# 11-_Ethernet_MAC.net
KiCad netlist of a schematic drawn in Altium Designer
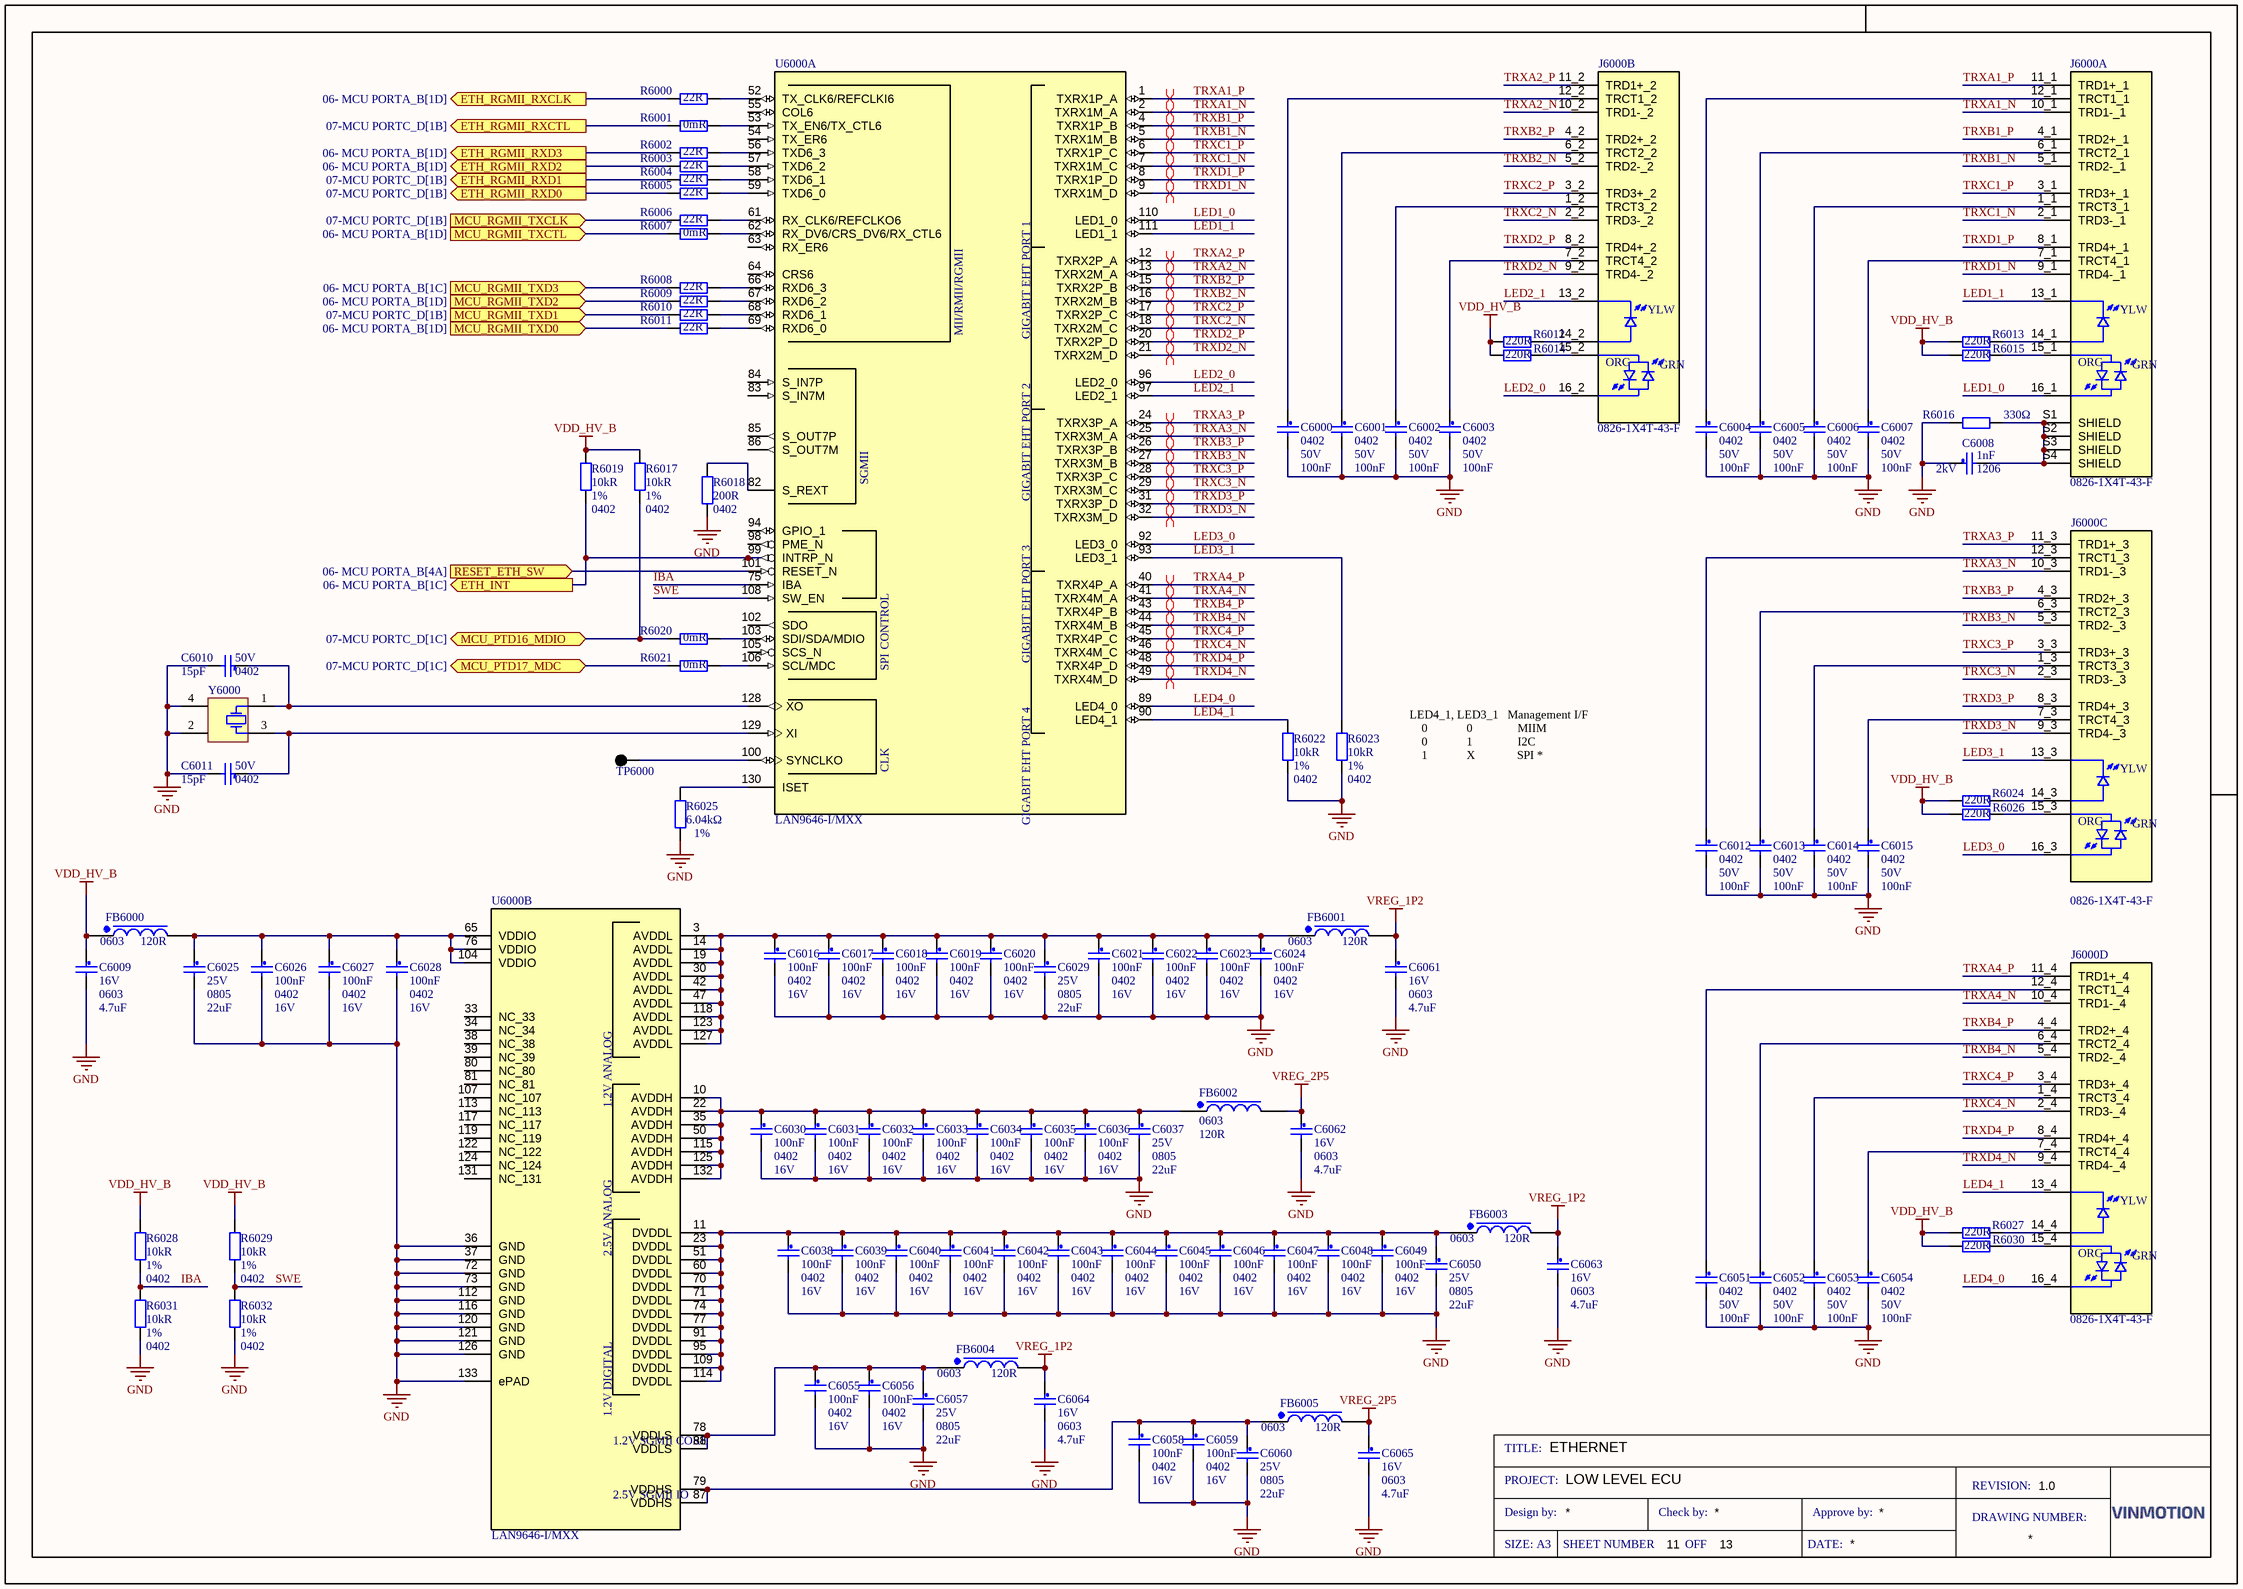
[diagram p0: 11- Ethernet MAC.SchDoc]

(export (version "E")
  (design (tool "Eeschema 10.0.6"))
  (components
    (comp (ref "C6000")
      (value "CL05B104KB54PNC")
      (footprint "CAP0402")
      (description "CAP CER 100nF 50V X7R 0402")
      (fields
        (field (name "CASE/PACKAGE") "0402")
        (field (name "VOLTAGE RATING") "50V")
        (field (name "CAPACITANCE") "100nF")
      )
      (libsource (lib "VMO_Lib") (part "CMP-00063-4"))
    )
    (comp (ref "C6001")
      (value "CL05B104KB54PNC")
      (footprint "CAP0402")
      (description "CAP CER 100nF 50V X7R 0402")
      (fields
        (field (name "CASE/PACKAGE") "0402")
        (field (name "VOLTAGE RATING") "50V")
        (field (name "CAPACITANCE") "100nF")
      )
      (libsource (lib "VMO_Lib") (part "CMP-00063-4"))
    )
    (comp (ref "C6002")
      (value "CL05B104KB54PNC")
      (footprint "CAP0402")
      (description "CAP CER 100nF 50V X7R 0402")
      (fields
        (field (name "CASE/PACKAGE") "0402")
        (field (name "VOLTAGE RATING") "50V")
        (field (name "CAPACITANCE") "100nF")
      )
      (libsource (lib "VMO_Lib") (part "CMP-00063-4"))
    )
    (comp (ref "C6003")
      (value "CL05B104KB54PNC")
      (footprint "CAP0402")
      (description "CAP CER 100nF 50V X7R 0402")
      (fields
        (field (name "CASE/PACKAGE") "0402")
        (field (name "VOLTAGE RATING") "50V")
        (field (name "CAPACITANCE") "100nF")
      )
      (libsource (lib "VMO_Lib") (part "CMP-00063-4"))
    )
    (comp (ref "C6004")
      (value "CL05B104KB54PNC")
      (footprint "CAP0402")
      (description "CAP CER 100nF 50V X7R 0402")
      (fields
        (field (name "CASE/PACKAGE") "0402")
        (field (name "VOLTAGE RATING") "50V")
        (field (name "CAPACITANCE") "100nF")
      )
      (libsource (lib "VMO_Lib") (part "CMP-00063-4"))
    )
    (comp (ref "C6005")
      (value "CL05B104KB54PNC")
      (footprint "CAP0402")
      (description "CAP CER 100nF 50V X7R 0402")
      (fields
        (field (name "CASE/PACKAGE") "0402")
        (field (name "VOLTAGE RATING") "50V")
        (field (name "CAPACITANCE") "100nF")
      )
      (libsource (lib "VMO_Lib") (part "CMP-00063-4"))
    )
    (comp (ref "C6006")
      (value "CL05B104KB54PNC")
      (footprint "CAP0402")
      (description "CAP CER 100nF 50V X7R 0402")
      (fields
        (field (name "CASE/PACKAGE") "0402")
        (field (name "VOLTAGE RATING") "50V")
        (field (name "CAPACITANCE") "100nF")
      )
      (libsource (lib "VMO_Lib") (part "CMP-00063-4"))
    )
    (comp (ref "C6007")
      (value "CL05B104KB54PNC")
      (footprint "CAP0402")
      (description "CAP CER 100nF 50V X7R 0402")
      (fields
        (field (name "CASE/PACKAGE") "0402")
        (field (name "VOLTAGE RATING") "50V")
        (field (name "CAPACITANCE") "100nF")
      )
      (libsource (lib "VMO_Lib") (part "CMP-00063-4"))
    )
    (comp (ref "C6008")
      (value "C1206C102KGRACAUTO")
      (footprint "CAP1206")
      (description "CAP CER 1000PF 2KV X7R 1206")
      (fields
        (field (name "TOLERANCE") "10%")
        (field (name "VOLTAGE RATING") "2kV")
        (field (name "CASE/PACKAGE") "1206")
        (field (name "CAPACITANCE") "1nF")
      )
      (libsource (lib "VMO_Lib") (part "CMP-00118-3"))
    )
    (comp (ref "C6009")
      (value "GRT188C81C475KE13D")
      (footprint "CAP0603")
      (description "CAP CER 4.7uF 16V 10% X6S 0603 SMD")
      (fields
        (field (name "TOLERANCE") "10%")
        (field (name "VOLTAGE RATING") "16V")
        (field (name "CASE/PACKAGE") "0603")
        (field (name "CAPACITANCE") "4.7uF")
      )
      (libsource (lib "VMO_Lib") (part "CMP-00351-2"))
    )
    (comp (ref "C6010")
      (value "GCM1555C1H150JA16D")
      (footprint "CAP0402")
      (description "CAP CER 15pF 50V 5% C0G 0402 SMD")
      (fields
        (field (name "TOLERANCE") "5%")
        (field (name "VOLTAGE RATING") "50V")
        (field (name "CASE/PACKAGE") "0402")
        (field (name "CAPACITANCE") "15pF")
      )
      (libsource (lib "VMO_Lib") (part "CMP-00205-2"))
    )
    (comp (ref "C6011")
      (value "GCM1555C1H150JA16D")
      (footprint "CAP0402")
      (description "CAP CER 15pF 50V 5% C0G 0402 SMD")
      (fields
        (field (name "TOLERANCE") "5%")
        (field (name "VOLTAGE RATING") "50V")
        (field (name "CASE/PACKAGE") "0402")
        (field (name "CAPACITANCE") "15pF")
      )
      (libsource (lib "VMO_Lib") (part "CMP-00205-2"))
    )
    (comp (ref "C6012")
      (value "CL05B104KB54PNC")
      (footprint "CAP0402")
      (description "CAP CER 100nF 50V X7R 0402")
      (fields
        (field (name "CASE/PACKAGE") "0402")
        (field (name "VOLTAGE RATING") "50V")
        (field (name "CAPACITANCE") "100nF")
      )
      (libsource (lib "VMO_Lib") (part "CMP-00063-4"))
    )
    (comp (ref "C6013")
      (value "CL05B104KB54PNC")
      (footprint "CAP0402")
      (description "CAP CER 100nF 50V X7R 0402")
      (fields
        (field (name "CASE/PACKAGE") "0402")
        (field (name "VOLTAGE RATING") "50V")
        (field (name "CAPACITANCE") "100nF")
      )
      (libsource (lib "VMO_Lib") (part "CMP-00063-4"))
    )
    (comp (ref "C6014")
      (value "CL05B104KB54PNC")
      (footprint "CAP0402")
      (description "CAP CER 100nF 50V X7R 0402")
      (fields
        (field (name "CASE/PACKAGE") "0402")
        (field (name "VOLTAGE RATING") "50V")
        (field (name "CAPACITANCE") "100nF")
      )
      (libsource (lib "VMO_Lib") (part "CMP-00063-4"))
    )
    (comp (ref "C6015")
      (value "CL05B104KB54PNC")
      (footprint "CAP0402")
      (description "CAP CER 100nF 50V X7R 0402")
      (fields
        (field (name "CASE/PACKAGE") "0402")
        (field (name "VOLTAGE RATING") "50V")
        (field (name "CAPACITANCE") "100nF")
      )
      (libsource (lib "VMO_Lib") (part "CMP-00063-4"))
    )
    (comp (ref "C6016")
      (value "0402YC104KAT2A")
      (footprint "CAP0402")
      (description "CAP CER 0.1UF 16V X7R 0402")
      (fields
        (field (name "CAPACITANCE") "100nF")
        (field (name "CASE/PACKAGE") "0402")
        (field (name "VOLTAGE RATING (DC)") "16V")
      )
      (libsource (lib "VMO_Lib") (part "CMP-00988-1"))
    )
    (comp (ref "C6017")
      (value "0402YC104KAT2A")
      (footprint "CAP0402")
      (description "CAP CER 0.1UF 16V X7R 0402")
      (fields
        (field (name "CAPACITANCE") "100nF")
        (field (name "CASE/PACKAGE") "0402")
        (field (name "VOLTAGE RATING (DC)") "16V")
      )
      (libsource (lib "VMO_Lib") (part "CMP-00988-1"))
    )
    (comp (ref "C6018")
      (value "0402YC104KAT2A")
      (footprint "CAP0402")
      (description "CAP CER 0.1UF 16V X7R 0402")
      (fields
        (field (name "CAPACITANCE") "100nF")
        (field (name "CASE/PACKAGE") "0402")
        (field (name "VOLTAGE RATING (DC)") "16V")
      )
      (libsource (lib "VMO_Lib") (part "CMP-00988-1"))
    )
    (comp (ref "C6019")
      (value "0402YC104KAT2A")
      (footprint "CAP0402")
      (description "CAP CER 0.1UF 16V X7R 0402")
      (fields
        (field (name "CAPACITANCE") "100nF")
        (field (name "CASE/PACKAGE") "0402")
        (field (name "VOLTAGE RATING (DC)") "16V")
      )
      (libsource (lib "VMO_Lib") (part "CMP-00988-1"))
    )
    (comp (ref "C6020")
      (value "0402YC104KAT2A")
      (footprint "CAP0402")
      (description "CAP CER 0.1UF 16V X7R 0402")
      (fields
        (field (name "CAPACITANCE") "100nF")
        (field (name "CASE/PACKAGE") "0402")
        (field (name "VOLTAGE RATING (DC)") "16V")
      )
      (libsource (lib "VMO_Lib") (part "CMP-00988-1"))
    )
    (comp (ref "C6021")
      (value "0402YC104KAT2A")
      (footprint "CAP0402")
      (description "CAP CER 0.1UF 16V X7R 0402")
      (fields
        (field (name "CAPACITANCE") "100nF")
        (field (name "CASE/PACKAGE") "0402")
        (field (name "VOLTAGE RATING (DC)") "16V")
      )
      (libsource (lib "VMO_Lib") (part "CMP-00988-1"))
    )
    (comp (ref "C6022")
      (value "0402YC104KAT2A")
      (footprint "CAP0402")
      (description "CAP CER 0.1UF 16V X7R 0402")
      (fields
        (field (name "CAPACITANCE") "100nF")
        (field (name "CASE/PACKAGE") "0402")
        (field (name "VOLTAGE RATING (DC)") "16V")
      )
      (libsource (lib "VMO_Lib") (part "CMP-00988-1"))
    )
    (comp (ref "C6023")
      (value "0402YC104KAT2A")
      (footprint "CAP0402")
      (description "CAP CER 0.1UF 16V X7R 0402")
      (fields
        (field (name "CAPACITANCE") "100nF")
        (field (name "CASE/PACKAGE") "0402")
        (field (name "VOLTAGE RATING (DC)") "16V")
      )
      (libsource (lib "VMO_Lib") (part "CMP-00988-1"))
    )
    (comp (ref "C6024")
      (value "0402YC104KAT2A")
      (footprint "CAP0402")
      (description "CAP CER 0.1UF 16V X7R 0402")
      (fields
        (field (name "CAPACITANCE") "100nF")
        (field (name "CASE/PACKAGE") "0402")
        (field (name "VOLTAGE RATING (DC)") "16V")
      )
      (libsource (lib "VMO_Lib") (part "CMP-00988-1"))
    )
    (comp (ref "C6025")
      (value "GRM21BR61E226ME44K")
      (footprint "CAP0805")
      (description "CAP CER 22uF 25V 20% X5R 0805 SMD")
      (fields
        (field (name "TOLERANCE") "20%")
        (field (name "VOLTAGE RATING") "25V")
        (field (name "CASE/PACKAGE") "0805")
        (field (name "CAPACITANCE") "22uF")
      )
      (libsource (lib "VMO_Lib") (part "CMP-ROOT-0068-6"))
    )
    (comp (ref "C6026")
      (value "0402YC104KAT2A")
      (footprint "CAP0402")
      (description "CAP CER 0.1UF 16V X7R 0402")
      (fields
        (field (name "CAPACITANCE") "100nF")
        (field (name "CASE/PACKAGE") "0402")
        (field (name "VOLTAGE RATING (DC)") "16V")
      )
      (libsource (lib "VMO_Lib") (part "CMP-00988-1"))
    )
    (comp (ref "C6027")
      (value "0402YC104KAT2A")
      (footprint "CAP0402")
      (description "CAP CER 0.1UF 16V X7R 0402")
      (fields
        (field (name "CAPACITANCE") "100nF")
        (field (name "CASE/PACKAGE") "0402")
        (field (name "VOLTAGE RATING (DC)") "16V")
      )
      (libsource (lib "VMO_Lib") (part "CMP-00988-1"))
    )
    (comp (ref "C6028")
      (value "0402YC104KAT2A")
      (footprint "CAP0402")
      (description "CAP CER 0.1UF 16V X7R 0402")
      (fields
        (field (name "CAPACITANCE") "100nF")
        (field (name "CASE/PACKAGE") "0402")
        (field (name "VOLTAGE RATING (DC)") "16V")
      )
      (libsource (lib "VMO_Lib") (part "CMP-00988-1"))
    )
    (comp (ref "C6029")
      (value "GRM21BR61E226ME44K")
      (footprint "CAP0805")
      (description "CAP CER 22uF 25V 20% X5R 0805 SMD")
      (fields
        (field (name "TOLERANCE") "20%")
        (field (name "VOLTAGE RATING") "25V")
        (field (name "CASE/PACKAGE") "0805")
        (field (name "CAPACITANCE") "22uF")
      )
      (libsource (lib "VMO_Lib") (part "CMP-ROOT-0068-6"))
    )
    (comp (ref "C6030")
      (value "0402YC104KAT2A")
      (footprint "CAP0402")
      (description "CAP CER 0.1UF 16V X7R 0402")
      (fields
        (field (name "CAPACITANCE") "100nF")
        (field (name "CASE/PACKAGE") "0402")
        (field (name "VOLTAGE RATING (DC)") "16V")
      )
      (libsource (lib "VMO_Lib") (part "CMP-00988-1"))
    )
    (comp (ref "C6031")
      (value "0402YC104KAT2A")
      (footprint "CAP0402")
      (description "CAP CER 0.1UF 16V X7R 0402")
      (fields
        (field (name "CAPACITANCE") "100nF")
        (field (name "CASE/PACKAGE") "0402")
        (field (name "VOLTAGE RATING (DC)") "16V")
      )
      (libsource (lib "VMO_Lib") (part "CMP-00988-1"))
    )
    (comp (ref "C6032")
      (value "0402YC104KAT2A")
      (footprint "CAP0402")
      (description "CAP CER 0.1UF 16V X7R 0402")
      (fields
        (field (name "CAPACITANCE") "100nF")
        (field (name "CASE/PACKAGE") "0402")
        (field (name "VOLTAGE RATING (DC)") "16V")
      )
      (libsource (lib "VMO_Lib") (part "CMP-00988-1"))
    )
    (comp (ref "C6033")
      (value "0402YC104KAT2A")
      (footprint "CAP0402")
      (description "CAP CER 0.1UF 16V X7R 0402")
      (fields
        (field (name "CAPACITANCE") "100nF")
        (field (name "CASE/PACKAGE") "0402")
        (field (name "VOLTAGE RATING (DC)") "16V")
      )
      (libsource (lib "VMO_Lib") (part "CMP-00988-1"))
    )
    (comp (ref "C6034")
      (value "0402YC104KAT2A")
      (footprint "CAP0402")
      (description "CAP CER 0.1UF 16V X7R 0402")
      (fields
        (field (name "CAPACITANCE") "100nF")
        (field (name "CASE/PACKAGE") "0402")
        (field (name "VOLTAGE RATING (DC)") "16V")
      )
      (libsource (lib "VMO_Lib") (part "CMP-00988-1"))
    )
    (comp (ref "C6035")
      (value "0402YC104KAT2A")
      (footprint "CAP0402")
      (description "CAP CER 0.1UF 16V X7R 0402")
      (fields
        (field (name "CAPACITANCE") "100nF")
        (field (name "CASE/PACKAGE") "0402")
        (field (name "VOLTAGE RATING (DC)") "16V")
      )
      (libsource (lib "VMO_Lib") (part "CMP-00988-1"))
    )
    (comp (ref "C6036")
      (value "0402YC104KAT2A")
      (footprint "CAP0402")
      (description "CAP CER 0.1UF 16V X7R 0402")
      (fields
        (field (name "CAPACITANCE") "100nF")
        (field (name "CASE/PACKAGE") "0402")
        (field (name "VOLTAGE RATING (DC)") "16V")
      )
      (libsource (lib "VMO_Lib") (part "CMP-00988-1"))
    )
    (comp (ref "C6037")
      (value "GRM21BR61E226ME44K")
      (footprint "CAP0805")
      (description "CAP CER 22uF 25V 20% X5R 0805 SMD")
      (fields
        (field (name "TOLERANCE") "20%")
        (field (name "VOLTAGE RATING") "25V")
        (field (name "CASE/PACKAGE") "0805")
        (field (name "CAPACITANCE") "22uF")
      )
      (libsource (lib "VMO_Lib") (part "CMP-ROOT-0068-6"))
    )
    (comp (ref "C6038")
      (value "0402YC104KAT2A")
      (footprint "CAP0402")
      (description "CAP CER 0.1UF 16V X7R 0402")
      (fields
        (field (name "CAPACITANCE") "100nF")
        (field (name "CASE/PACKAGE") "0402")
        (field (name "VOLTAGE RATING (DC)") "16V")
      )
      (libsource (lib "VMO_Lib") (part "CMP-00988-1"))
    )
    (comp (ref "C6039")
      (value "0402YC104KAT2A")
      (footprint "CAP0402")
      (description "CAP CER 0.1UF 16V X7R 0402")
      (fields
        (field (name "CAPACITANCE") "100nF")
        (field (name "CASE/PACKAGE") "0402")
        (field (name "VOLTAGE RATING (DC)") "16V")
      )
      (libsource (lib "VMO_Lib") (part "CMP-00988-1"))
    )
    (comp (ref "C6040")
      (value "0402YC104KAT2A")
      (footprint "CAP0402")
      (description "CAP CER 0.1UF 16V X7R 0402")
      (fields
        (field (name "CAPACITANCE") "100nF")
        (field (name "CASE/PACKAGE") "0402")
        (field (name "VOLTAGE RATING (DC)") "16V")
      )
      (libsource (lib "VMO_Lib") (part "CMP-00988-1"))
    )
    (comp (ref "C6041")
      (value "0402YC104KAT2A")
      (footprint "CAP0402")
      (description "CAP CER 0.1UF 16V X7R 0402")
      (fields
        (field (name "CAPACITANCE") "100nF")
        (field (name "CASE/PACKAGE") "0402")
        (field (name "VOLTAGE RATING (DC)") "16V")
      )
      (libsource (lib "VMO_Lib") (part "CMP-00988-1"))
    )
    (comp (ref "C6042")
      (value "0402YC104KAT2A")
      (footprint "CAP0402")
      (description "CAP CER 0.1UF 16V X7R 0402")
      (fields
        (field (name "CAPACITANCE") "100nF")
        (field (name "CASE/PACKAGE") "0402")
        (field (name "VOLTAGE RATING (DC)") "16V")
      )
      (libsource (lib "VMO_Lib") (part "CMP-00988-1"))
    )
    (comp (ref "C6043")
      (value "0402YC104KAT2A")
      (footprint "CAP0402")
      (description "CAP CER 0.1UF 16V X7R 0402")
      (fields
        (field (name "CAPACITANCE") "100nF")
        (field (name "CASE/PACKAGE") "0402")
        (field (name "VOLTAGE RATING (DC)") "16V")
      )
      (libsource (lib "VMO_Lib") (part "CMP-00988-1"))
    )
    (comp (ref "C6044")
      (value "0402YC104KAT2A")
      (footprint "CAP0402")
      (description "CAP CER 0.1UF 16V X7R 0402")
      (fields
        (field (name "CAPACITANCE") "100nF")
        (field (name "CASE/PACKAGE") "0402")
        (field (name "VOLTAGE RATING (DC)") "16V")
      )
      (libsource (lib "VMO_Lib") (part "CMP-00988-1"))
    )
    (comp (ref "C6045")
      (value "0402YC104KAT2A")
      (footprint "CAP0402")
      (description "CAP CER 0.1UF 16V X7R 0402")
      (fields
        (field (name "CAPACITANCE") "100nF")
        (field (name "CASE/PACKAGE") "0402")
        (field (name "VOLTAGE RATING (DC)") "16V")
      )
      (libsource (lib "VMO_Lib") (part "CMP-00988-1"))
    )
    (comp (ref "C6046")
      (value "0402YC104KAT2A")
      (footprint "CAP0402")
      (description "CAP CER 0.1UF 16V X7R 0402")
      (fields
        (field (name "CAPACITANCE") "100nF")
        (field (name "CASE/PACKAGE") "0402")
        (field (name "VOLTAGE RATING (DC)") "16V")
      )
      (libsource (lib "VMO_Lib") (part "CMP-00988-1"))
    )
    (comp (ref "C6047")
      (value "0402YC104KAT2A")
      (footprint "CAP0402")
      (description "CAP CER 0.1UF 16V X7R 0402")
      (fields
        (field (name "CAPACITANCE") "100nF")
        (field (name "CASE/PACKAGE") "0402")
        (field (name "VOLTAGE RATING (DC)") "16V")
      )
      (libsource (lib "VMO_Lib") (part "CMP-00988-1"))
    )
    (comp (ref "C6048")
      (value "0402YC104KAT2A")
      (footprint "CAP0402")
      (description "CAP CER 0.1UF 16V X7R 0402")
      (fields
        (field (name "CAPACITANCE") "100nF")
        (field (name "CASE/PACKAGE") "0402")
        (field (name "VOLTAGE RATING (DC)") "16V")
      )
      (libsource (lib "VMO_Lib") (part "CMP-00988-1"))
    )
    (comp (ref "C6049")
      (value "0402YC104KAT2A")
      (footprint "CAP0402")
      (description "CAP CER 0.1UF 16V X7R 0402")
      (fields
        (field (name "CAPACITANCE") "100nF")
        (field (name "CASE/PACKAGE") "0402")
        (field (name "VOLTAGE RATING (DC)") "16V")
      )
      (libsource (lib "VMO_Lib") (part "CMP-00988-1"))
    )
    (comp (ref "C6050")
      (value "GRM21BR61E226ME44K")
      (footprint "CAP0805")
      (description "CAP CER 22uF 25V 20% X5R 0805 SMD")
      (fields
        (field (name "TOLERANCE") "20%")
        (field (name "VOLTAGE RATING") "25V")
        (field (name "CASE/PACKAGE") "0805")
        (field (name "CAPACITANCE") "22uF")
      )
      (libsource (lib "VMO_Lib") (part "CMP-ROOT-0068-6"))
    )
    (comp (ref "C6051")
      (value "CL05B104KB54PNC")
      (footprint "CAP0402")
      (description "CAP CER 100nF 50V X7R 0402")
      (fields
        (field (name "CASE/PACKAGE") "0402")
        (field (name "VOLTAGE RATING") "50V")
        (field (name "CAPACITANCE") "100nF")
      )
      (libsource (lib "VMO_Lib") (part "CMP-00063-4"))
    )
    (comp (ref "C6052")
      (value "CL05B104KB54PNC")
      (footprint "CAP0402")
      (description "CAP CER 100nF 50V X7R 0402")
      (fields
        (field (name "CASE/PACKAGE") "0402")
        (field (name "VOLTAGE RATING") "50V")
        (field (name "CAPACITANCE") "100nF")
      )
      (libsource (lib "VMO_Lib") (part "CMP-00063-4"))
    )
    (comp (ref "C6053")
      (value "CL05B104KB54PNC")
      (footprint "CAP0402")
      (description "CAP CER 100nF 50V X7R 0402")
      (fields
        (field (name "CASE/PACKAGE") "0402")
        (field (name "VOLTAGE RATING") "50V")
        (field (name "CAPACITANCE") "100nF")
      )
      (libsource (lib "VMO_Lib") (part "CMP-00063-4"))
    )
    (comp (ref "C6054")
      (value "CL05B104KB54PNC")
      (footprint "CAP0402")
      (description "CAP CER 100nF 50V X7R 0402")
      (fields
        (field (name "CASE/PACKAGE") "0402")
        (field (name "VOLTAGE RATING") "50V")
        (field (name "CAPACITANCE") "100nF")
      )
      (libsource (lib "VMO_Lib") (part "CMP-00063-4"))
    )
    (comp (ref "C6055")
      (value "0402YC104KAT2A")
      (footprint "CAP0402")
      (description "CAP CER 0.1UF 16V X7R 0402")
      (fields
        (field (name "CAPACITANCE") "100nF")
        (field (name "CASE/PACKAGE") "0402")
        (field (name "VOLTAGE RATING (DC)") "16V")
      )
      (libsource (lib "VMO_Lib") (part "CMP-00988-1"))
    )
    (comp (ref "C6056")
      (value "0402YC104KAT2A")
      (footprint "CAP0402")
      (description "CAP CER 0.1UF 16V X7R 0402")
      (fields
        (field (name "CAPACITANCE") "100nF")
        (field (name "CASE/PACKAGE") "0402")
        (field (name "VOLTAGE RATING (DC)") "16V")
      )
      (libsource (lib "VMO_Lib") (part "CMP-00988-1"))
    )
    (comp (ref "C6057")
      (value "GRM21BR61E226ME44K")
      (footprint "CAP0805")
      (description "CAP CER 22uF 25V 20% X5R 0805 SMD")
      (fields
        (field (name "TOLERANCE") "20%")
        (field (name "VOLTAGE RATING") "25V")
        (field (name "CASE/PACKAGE") "0805")
        (field (name "CAPACITANCE") "22uF")
      )
      (libsource (lib "VMO_Lib") (part "CMP-ROOT-0068-6"))
    )
    (comp (ref "C6058")
      (value "0402YC104KAT2A")
      (footprint "CAP0402")
      (description "CAP CER 0.1UF 16V X7R 0402")
      (fields
        (field (name "CAPACITANCE") "100nF")
        (field (name "CASE/PACKAGE") "0402")
        (field (name "VOLTAGE RATING (DC)") "16V")
      )
      (libsource (lib "VMO_Lib") (part "CMP-00988-1"))
    )
    (comp (ref "C6059")
      (value "0402YC104KAT2A")
      (footprint "CAP0402")
      (description "CAP CER 0.1UF 16V X7R 0402")
      (fields
        (field (name "CAPACITANCE") "100nF")
        (field (name "CASE/PACKAGE") "0402")
        (field (name "VOLTAGE RATING (DC)") "16V")
      )
      (libsource (lib "VMO_Lib") (part "CMP-00988-1"))
    )
    (comp (ref "C6060")
      (value "GRM21BR61E226ME44K")
      (footprint "CAP0805")
      (description "CAP CER 22uF 25V 20% X5R 0805 SMD")
      (fields
        (field (name "TOLERANCE") "20%")
        (field (name "VOLTAGE RATING") "25V")
        (field (name "CASE/PACKAGE") "0805")
        (field (name "CAPACITANCE") "22uF")
      )
      (libsource (lib "VMO_Lib") (part "CMP-ROOT-0068-6"))
    )
    (comp (ref "C6061")
      (value "GRT188C81C475KE13D")
      (footprint "CAP0603")
      (description "CAP CER 4.7uF 16V 10% X6S 0603 SMD")
      (fields
        (field (name "TOLERANCE") "10%")
        (field (name "VOLTAGE RATING") "16V")
        (field (name "CASE/PACKAGE") "0603")
        (field (name "CAPACITANCE") "4.7uF")
      )
      (libsource (lib "VMO_Lib") (part "CMP-00351-2"))
    )
    (comp (ref "C6062")
      (value "GRT188C81C475KE13D")
      (footprint "CAP0603")
      (description "CAP CER 4.7uF 16V 10% X6S 0603 SMD")
      (fields
        (field (name "TOLERANCE") "10%")
        (field (name "VOLTAGE RATING") "16V")
        (field (name "CASE/PACKAGE") "0603")
        (field (name "CAPACITANCE") "4.7uF")
      )
      (libsource (lib "VMO_Lib") (part "CMP-00351-2"))
    )
    (comp (ref "C6063")
      (value "GRT188C81C475KE13D")
      (footprint "CAP0603")
      (description "CAP CER 4.7uF 16V 10% X6S 0603 SMD")
      (fields
        (field (name "TOLERANCE") "10%")
        (field (name "VOLTAGE RATING") "16V")
        (field (name "CASE/PACKAGE") "0603")
        (field (name "CAPACITANCE") "4.7uF")
      )
      (libsource (lib "VMO_Lib") (part "CMP-00351-2"))
    )
    (comp (ref "C6064")
      (value "GRT188C81C475KE13D")
      (footprint "CAP0603")
      (description "CAP CER 4.7uF 16V 10% X6S 0603 SMD")
      (fields
        (field (name "TOLERANCE") "10%")
        (field (name "VOLTAGE RATING") "16V")
        (field (name "CASE/PACKAGE") "0603")
        (field (name "CAPACITANCE") "4.7uF")
      )
      (libsource (lib "VMO_Lib") (part "CMP-00351-2"))
    )
    (comp (ref "C6065")
      (value "GRT188C81C475KE13D")
      (footprint "CAP0603")
      (description "CAP CER 4.7uF 16V 10% X6S 0603 SMD")
      (fields
        (field (name "TOLERANCE") "10%")
        (field (name "VOLTAGE RATING") "16V")
        (field (name "CASE/PACKAGE") "0603")
        (field (name "CAPACITANCE") "4.7uF")
      )
      (libsource (lib "VMO_Lib") (part "CMP-00351-2"))
    )
    (comp (ref "FB6000")
      (value "BLM18KG121TH1D")
      (footprint "FB0603")
      (description "FERRITE BEAD 120 OHM 0603 1LN")
      (fields (field (name "CASE/PACKAGE") "0603") (field (name "IMPEDANCE") "120R"))
      (libsource (lib "VMO_Lib") (part "CMP-ROOT-0013-6"))
    )
    (comp (ref "FB6001")
      (value "BLM18KG121TH1D")
      (footprint "FB0603")
      (description "FERRITE BEAD 120 OHM 0603 1LN")
      (fields (field (name "CASE/PACKAGE") "0603") (field (name "IMPEDANCE") "120R"))
      (libsource (lib "VMO_Lib") (part "CMP-ROOT-0013-6"))
    )
    (comp (ref "FB6002")
      (value "BLM18KG121TH1D")
      (footprint "FB0603")
      (description "FERRITE BEAD 120 OHM 0603 1LN")
      (fields (field (name "CASE/PACKAGE") "0603") (field (name "IMPEDANCE") "120R"))
      (libsource (lib "VMO_Lib") (part "CMP-ROOT-0013-6"))
    )
    (comp (ref "FB6003")
      (value "BLM18KG121TH1D")
      (footprint "FB0603")
      (description "FERRITE BEAD 120 OHM 0603 1LN")
      (fields (field (name "CASE/PACKAGE") "0603") (field (name "IMPEDANCE") "120R"))
      (libsource (lib "VMO_Lib") (part "CMP-ROOT-0013-6"))
    )
    (comp (ref "FB6004")
      (value "BLM18KG121TH1D")
      (footprint "FB0603")
      (description "FERRITE BEAD 120 OHM 0603 1LN")
      (fields (field (name "CASE/PACKAGE") "0603") (field (name "IMPEDANCE") "120R"))
      (libsource (lib "VMO_Lib") (part "CMP-ROOT-0013-6"))
    )
    (comp (ref "FB6005")
      (value "BLM18KG121TH1D")
      (footprint "FB0603")
      (description "FERRITE BEAD 120 OHM 0603 1LN")
      (fields (field (name "CASE/PACKAGE") "0603") (field (name "IMPEDANCE") "120R"))
      (libsource (lib "VMO_Lib") (part "CMP-ROOT-0013-6"))
    )
    (comp (ref "J6000")
      (value "0826-1X4T-43-F")
      (footprint "CONN JACK 4PORT PCB")
      (description "CONN JACK 4PORT PCB")
      (fields (field (name "MANUFACTURER") "Bel Fuse"))
      (libsource (lib "VMO_Lib") (part "CMP-01175-1"))
    )
    (comp (ref "R6000")
      (value "CRCW040222R0JNED")
      (footprint "RES0402")
      (description "RES SMD 22 OHM 5% 1/16W 0402")
      (fields (field (name "TOLERANCE") "5%") (field (name "RESISTANCE") "22R"))
      (libsource (lib "VMO_Lib") (part "CMP-00237-1"))
    )
    (comp (ref "R6001")
      (value "RMCF0402ZT0R00")
      (footprint "RES0402")
      (description "RES 0R 1/16W 1% 0402 SMD")
      (fields (field (name "RESISTANCE") "0mR"))
      (libsource (lib "VMO_Lib") (part "CMP-ROOT-0037-10"))
    )
    (comp (ref "R6002")
      (value "CRCW040222R0JNED")
      (footprint "RES0402")
      (description "RES SMD 22 OHM 5% 1/16W 0402")
      (fields (field (name "TOLERANCE") "5%") (field (name "RESISTANCE") "22R"))
      (libsource (lib "VMO_Lib") (part "CMP-00237-1"))
    )
    (comp (ref "R6003")
      (value "CRCW040222R0JNED")
      (footprint "RES0402")
      (description "RES SMD 22 OHM 5% 1/16W 0402")
      (fields (field (name "TOLERANCE") "5%") (field (name "RESISTANCE") "22R"))
      (libsource (lib "VMO_Lib") (part "CMP-00237-1"))
    )
    (comp (ref "R6004")
      (value "CRCW040222R0JNED")
      (footprint "RES0402")
      (description "RES SMD 22 OHM 5% 1/16W 0402")
      (fields (field (name "TOLERANCE") "5%") (field (name "RESISTANCE") "22R"))
      (libsource (lib "VMO_Lib") (part "CMP-00237-1"))
    )
    (comp (ref "R6005")
      (value "CRCW040222R0JNED")
      (footprint "RES0402")
      (description "RES SMD 22 OHM 5% 1/16W 0402")
      (fields (field (name "TOLERANCE") "5%") (field (name "RESISTANCE") "22R"))
      (libsource (lib "VMO_Lib") (part "CMP-00237-1"))
    )
    (comp (ref "R6006")
      (value "CRCW040222R0JNED")
      (footprint "RES0402")
      (description "RES SMD 22 OHM 5% 1/16W 0402")
      (fields (field (name "TOLERANCE") "5%") (field (name "RESISTANCE") "22R"))
      (libsource (lib "VMO_Lib") (part "CMP-00237-1"))
    )
    (comp (ref "R6007")
      (value "RMCF0402ZT0R00")
      (footprint "RES0402")
      (description "RES 0R 1/16W 1% 0402 SMD")
      (fields (field (name "RESISTANCE") "0mR"))
      (libsource (lib "VMO_Lib") (part "CMP-ROOT-0037-10"))
    )
    (comp (ref "R6008")
      (value "CRCW040222R0JNED")
      (footprint "RES0402")
      (description "RES SMD 22 OHM 5% 1/16W 0402")
      (fields (field (name "TOLERANCE") "5%") (field (name "RESISTANCE") "22R"))
      (libsource (lib "VMO_Lib") (part "CMP-00237-1"))
    )
    (comp (ref "R6009")
      (value "CRCW040222R0JNED")
      (footprint "RES0402")
      (description "RES SMD 22 OHM 5% 1/16W 0402")
      (fields (field (name "TOLERANCE") "5%") (field (name "RESISTANCE") "22R"))
      (libsource (lib "VMO_Lib") (part "CMP-00237-1"))
    )
    (comp (ref "R6010")
      (value "CRCW040222R0JNED")
      (footprint "RES0402")
      (description "RES SMD 22 OHM 5% 1/16W 0402")
      (fields (field (name "TOLERANCE") "5%") (field (name "RESISTANCE") "22R"))
      (libsource (lib "VMO_Lib") (part "CMP-00237-1"))
    )
    (comp (ref "R6011")
      (value "CRCW040222R0JNED")
      (footprint "RES0402")
      (description "RES SMD 22 OHM 5% 1/16W 0402")
      (fields (field (name "TOLERANCE") "5%") (field (name "RESISTANCE") "22R"))
      (libsource (lib "VMO_Lib") (part "CMP-00237-1"))
    )
    (comp (ref "R6012")
      (value "220R")
      (footprint "RES0402")
      (description "RES SMD 220 OHM 1% 1/10W 0402")
      (fields
        (field (name "MANUFACTURER") "Vishay")
        (field (name "MANUFACTURER PART NUMBER") "CRCW0402220RFKED")
      )
      (libsource (lib "VMO_Lib") (part "CMP-01126-1"))
    )
    (comp (ref "R6013")
      (value "220R")
      (footprint "RES0402")
      (description "RES SMD 220 OHM 1% 1/10W 0402")
      (fields
        (field (name "MANUFACTURER") "Vishay")
        (field (name "MANUFACTURER PART NUMBER") "CRCW0402220RFKED")
      )
      (libsource (lib "VMO_Lib") (part "CMP-01126-1"))
    )
    (comp (ref "R6014")
      (value "220R")
      (footprint "RES0402")
      (description "RES SMD 220 OHM 1% 1/10W 0402")
      (fields
        (field (name "MANUFACTURER") "Vishay")
        (field (name "MANUFACTURER PART NUMBER") "CRCW0402220RFKED")
      )
      (libsource (lib "VMO_Lib") (part "CMP-01126-1"))
    )
    (comp (ref "R6015")
      (value "220R")
      (footprint "RES0402")
      (description "RES SMD 220 OHM 1% 1/10W 0402")
      (fields
        (field (name "MANUFACTURER") "Vishay")
        (field (name "MANUFACTURER PART NUMBER") "CRCW0402220RFKED")
      )
      (libsource (lib "VMO_Lib") (part "CMP-01126-1"))
    )
    (comp (ref "R6016")
      (value "330Ω")
      (footprint "RES0603")
      (description "RES 330 OHM 5% 1/10W 0603")
      (fields
        (field (name "MANUFACTURER") "Yageo Group")
        (field (name "MANUFACTURER PART NUMBER") "RC0603JR-07330RL")
      )
      (libsource (lib "VMO_Lib") (part "CMP-01176-1"))
    )
    (comp (ref "R6017")
      (value "10kR")
      (footprint "RES0402")
      (description "RES 10K OHM 1% 1/16W 0402")
      (fields
        (field (name "MANUFACTURER") "Stackpole Electronics")
        (field (name "MANUFACTURER PART NUMBER") "RMCF0402FT10K0")
        (field (name "TOLERANCE") "1%")
        (field (name "CASE/PACKAGE") "0402")
      )
      (libsource (lib "VMO_Lib") (part "CMP-01105-1"))
    )
    (comp (ref "R6018")
      (value "AC0402FR-07200RL")
      (footprint "RES0402")
      (description "RES SMD 200 OHM 1% 1/16W 0402")
      (fields
        (field (name "TOLERANCE") "1%")
        (field (name "RESISTANCE") "200R")
        (field (name "CASE/PACKAGE") "0402")
      )
      (libsource (lib "VMO_Lib") (part "CMP-00798-1"))
    )
    (comp (ref "R6019")
      (value "10kR")
      (footprint "RES0402")
      (description "RES 10K OHM 1% 1/16W 0402")
      (fields
        (field (name "MANUFACTURER") "Stackpole Electronics")
        (field (name "MANUFACTURER PART NUMBER") "RMCF0402FT10K0")
        (field (name "TOLERANCE") "1%")
        (field (name "CASE/PACKAGE") "0402")
      )
      (libsource (lib "VMO_Lib") (part "CMP-01105-1"))
    )
    (comp (ref "R6020")
      (value "RMCF0402ZT0R00")
      (footprint "RES0402")
      (description "RES 0R 1/16W 1% 0402 SMD")
      (fields (field (name "RESISTANCE") "0mR"))
      (libsource (lib "VMO_Lib") (part "CMP-ROOT-0037-10"))
    )
    (comp (ref "R6021")
      (value "RMCF0402ZT0R00")
      (footprint "RES0402")
      (description "RES 0R 1/16W 1% 0402 SMD")
      (fields (field (name "RESISTANCE") "0mR"))
      (libsource (lib "VMO_Lib") (part "CMP-ROOT-0037-10"))
    )
    (comp (ref "R6022")
      (value "10kR")
      (footprint "RES0402")
      (description "RES 10K OHM 1% 1/16W 0402")
      (fields
        (field (name "MANUFACTURER") "Stackpole Electronics")
        (field (name "MANUFACTURER PART NUMBER") "RMCF0402FT10K0")
        (field (name "TOLERANCE") "1%")
        (field (name "CASE/PACKAGE") "0402")
      )
      (libsource (lib "VMO_Lib") (part "CMP-01105-1"))
    )
    (comp (ref "R6023")
      (value "10kR")
      (footprint "RES0402")
      (description "RES 10K OHM 1% 1/16W 0402")
      (fields
        (field (name "MANUFACTURER") "Stackpole Electronics")
        (field (name "MANUFACTURER PART NUMBER") "RMCF0402FT10K0")
        (field (name "TOLERANCE") "1%")
        (field (name "CASE/PACKAGE") "0402")
      )
      (libsource (lib "VMO_Lib") (part "CMP-01105-1"))
    )
    (comp (ref "R6024")
      (value "220R")
      (footprint "RES0402")
      (description "RES SMD 220 OHM 1% 1/10W 0402")
      (fields
        (field (name "MANUFACTURER") "Vishay")
        (field (name "MANUFACTURER PART NUMBER") "CRCW0402220RFKED")
      )
      (libsource (lib "VMO_Lib") (part "CMP-01126-1"))
    )
    (comp (ref "R6025")
      (value "6.04kΩ")
      (footprint "RES0402")
      (description "RES 6.04K OHM 1% 1/16W 0402")
      (fields
        (field (name "MANUFACTURER") "Vishay")
        (field (name "MANUFACTURER PART NUMBER") "CRCW04026K04FKEDC")
        (field (name "TOLERANCE") "1%")
      )
      (libsource (lib "VMO_Lib") (part "CMP-01177-1"))
    )
    (comp (ref "R6026")
      (value "220R")
      (footprint "RES0402")
      (description "RES SMD 220 OHM 1% 1/10W 0402")
      (fields
        (field (name "MANUFACTURER") "Vishay")
        (field (name "MANUFACTURER PART NUMBER") "CRCW0402220RFKED")
      )
      (libsource (lib "VMO_Lib") (part "CMP-01126-1"))
    )
    (comp (ref "R6027")
      (value "220R")
      (footprint "RES0402")
      (description "RES SMD 220 OHM 1% 1/10W 0402")
      (fields
        (field (name "MANUFACTURER") "Vishay")
        (field (name "MANUFACTURER PART NUMBER") "CRCW0402220RFKED")
      )
      (libsource (lib "VMO_Lib") (part "CMP-01126-1"))
    )
    (comp (ref "R6028")
      (value "10kR")
      (footprint "RES0402")
      (description "RES 10K OHM 1% 1/16W 0402")
      (fields
        (field (name "MANUFACTURER") "Stackpole Electronics")
        (field (name "MANUFACTURER PART NUMBER") "RMCF0402FT10K0")
        (field (name "TOLERANCE") "1%")
        (field (name "CASE/PACKAGE") "0402")
      )
      (libsource (lib "VMO_Lib") (part "CMP-01105-1"))
    )
    (comp (ref "R6029")
      (value "10kR")
      (footprint "RES0402")
      (description "RES 10K OHM 1% 1/16W 0402")
      (fields
        (field (name "MANUFACTURER") "Stackpole Electronics")
        (field (name "MANUFACTURER PART NUMBER") "RMCF0402FT10K0")
        (field (name "TOLERANCE") "1%")
        (field (name "CASE/PACKAGE") "0402")
      )
      (libsource (lib "VMO_Lib") (part "CMP-01105-1"))
    )
    (comp (ref "R6030")
      (value "220R")
      (footprint "RES0402")
      (description "RES SMD 220 OHM 1% 1/10W 0402")
      (fields
        (field (name "MANUFACTURER") "Vishay")
        (field (name "MANUFACTURER PART NUMBER") "CRCW0402220RFKED")
      )
      (libsource (lib "VMO_Lib") (part "CMP-01126-1"))
    )
    (comp (ref "R6031")
      (value "10kR")
      (footprint "RES0402")
      (description "RES 10K OHM 1% 1/16W 0402")
      (fields
        (field (name "MANUFACTURER") "Stackpole Electronics")
        (field (name "MANUFACTURER PART NUMBER") "RMCF0402FT10K0")
        (field (name "TOLERANCE") "1%")
        (field (name "CASE/PACKAGE") "0402")
      )
      (libsource (lib "VMO_Lib") (part "CMP-01105-1"))
    )
    (comp (ref "R6032")
      (value "10kR")
      (footprint "RES0402")
      (description "RES 10K OHM 1% 1/16W 0402")
      (fields
        (field (name "MANUFACTURER") "Stackpole Electronics")
        (field (name "MANUFACTURER PART NUMBER") "RMCF0402FT10K0")
        (field (name "TOLERANCE") "1%")
        (field (name "CASE/PACKAGE") "0402")
      )
      (libsource (lib "VMO_Lib") (part "CMP-01105-1"))
    )
    (comp (ref "TP6000")
      (value "TP")
      (footprint "TP-SMD-R1")
      (description "Test Point 1x1mm")
      (libsource (lib "VMO_Lib") (part "CMP-ROOT-0080-12"))
    )
    (comp (ref "U6000")
      (value "LAN9646-I/MXX")
      (footprint "132-VFQFN Dual Rows, Exposed Pad")
      (description "6-PORT GIGE MANAGED SWITCH WITH")
      (fields (field (name "MANUFACTURER") "Microchip"))
      (libsource (lib "VMO_Lib") (part "CMP-01174-1"))
    )
    (comp (ref "Y6000")
      (value "NX3225SA-25.000M-STD-CRS-2")
      (footprint "NDK_NX3225SA-25.000M-STD-CRS-2_R")
      (description "CRYSTAL 25.0000MHZ 8PF SMD")
      (libsource (lib "VMO_Lib") (part "CMP-00003-5"))
    )
  )
  (nets
    (net (code "1") (name "/ETH_INT") (class "Default")
      (node (ref "R6019") (pin "1") (pinfunction "1_1") (pintype "passive"))
      (node (ref "U6000") (pin "99") (pinfunction "INTRP_N_99") (pintype "output"))
    )
    (net (code "2") (name "/ETH_RGMII_RXCLK") (class "Default")
      (node (ref "R6000") (pin "1") (pinfunction "1_1") (pintype "passive"))
    )
    (net (code "3") (name "/ETH_RGMII_RXCTL") (class "Default")
      (node (ref "R6001") (pin "1") (pinfunction "1_1") (pintype "passive"))
    )
    (net (code "4") (name "/ETH_RGMII_RXD0") (class "Default")
      (node (ref "R6005") (pin "1") (pinfunction "1_1") (pintype "passive"))
    )
    (net (code "5") (name "/ETH_RGMII_RXD1") (class "Default")
      (node (ref "R6004") (pin "1") (pinfunction "1_1") (pintype "passive"))
    )
    (net (code "6") (name "/ETH_RGMII_RXD2") (class "Default")
      (node (ref "R6003") (pin "1") (pinfunction "1_1") (pintype "passive"))
    )
    (net (code "7") (name "/ETH_RGMII_RXD3") (class "Default")
      (node (ref "R6002") (pin "1") (pinfunction "1_1") (pintype "passive"))
    )
    (net (code "8") (name "/IBA") (class "Default")
      (node (ref "R6028") (pin "1") (pinfunction "1_1") (pintype "passive"))
      (node (ref "R6031") (pin "2") (pinfunction "2_2") (pintype "passive"))
      (node (ref "U6000") (pin "75") (pinfunction "IBA_75") (pintype "input"))
    )
    (net (code "9") (name "/LED1_0") (class "Default")
      (node (ref "J6000") (pin "16_1") (pinfunction "16_1_16_1") (pintype "passive"))
      (node (ref "U6000") (pin "110") (pinfunction "LED1_0_110") (pintype "bidirectional"))
    )
    (net (code "10") (name "/LED1_1") (class "Default")
      (node (ref "J6000") (pin "13_1") (pinfunction "13_1_13_1") (pintype "passive"))
      (node (ref "U6000") (pin "111") (pinfunction "LED1_1_111") (pintype "bidirectional"))
    )
    (net (code "11") (name "/LED2_0") (class "Default")
      (node (ref "J6000") (pin "16_2") (pinfunction "16_2_16_2") (pintype "passive"))
      (node (ref "U6000") (pin "96") (pinfunction "LED2_0_96") (pintype "bidirectional"))
    )
    (net (code "12") (name "/LED2_1") (class "Default")
      (node (ref "J6000") (pin "13_2") (pinfunction "13_2_13_2") (pintype "passive"))
      (node (ref "U6000") (pin "97") (pinfunction "LED2_1_97") (pintype "bidirectional"))
    )
    (net (code "13") (name "/LED3_0") (class "Default")
      (node (ref "J6000") (pin "16_3") (pinfunction "16_3_16_3") (pintype "passive"))
      (node (ref "U6000") (pin "92") (pinfunction "LED3_0_92") (pintype "bidirectional"))
    )
    (net (code "14") (name "/LED3_1") (class "Default")
      (node (ref "J6000") (pin "13_3") (pinfunction "13_3_13_3") (pintype "passive"))
      (node (ref "R6023") (pin "2") (pinfunction "2_2") (pintype "passive"))
      (node (ref "U6000") (pin "93") (pinfunction "LED3_1_93") (pintype "bidirectional"))
    )
    (net (code "15") (name "/LED4_0") (class "Default")
      (node (ref "J6000") (pin "16_4") (pinfunction "16_4_16_4") (pintype "passive"))
      (node (ref "U6000") (pin "89") (pinfunction "LED4_0_89") (pintype "bidirectional"))
    )
    (net (code "16") (name "/LED4_1") (class "Default")
      (node (ref "J6000") (pin "13_4") (pinfunction "13_4_13_4") (pintype "passive"))
      (node (ref "R6022") (pin "2") (pinfunction "2_2") (pintype "passive"))
      (node (ref "U6000") (pin "90") (pinfunction "LED4_1_90") (pintype "bidirectional"))
    )
    (net (code "17") (name "/MCU_PTD16_MDIO") (class "Default")
      (node (ref "R6017") (pin "1") (pinfunction "1_1") (pintype "passive"))
      (node (ref "R6020") (pin "1") (pinfunction "1_1") (pintype "passive"))
    )
    (net (code "18") (name "/MCU_PTD17_MDC") (class "Default")
      (node (ref "R6021") (pin "1") (pinfunction "1_1") (pintype "passive"))
    )
    (net (code "19") (name "/MCU_RGMII_TXCLK") (class "Default")
      (node (ref "R6006") (pin "1") (pinfunction "1_1") (pintype "passive"))
    )
    (net (code "20") (name "/MCU_RGMII_TXCTL") (class "Default")
      (node (ref "R6007") (pin "1") (pinfunction "1_1") (pintype "passive"))
    )
    (net (code "21") (name "/MCU_RGMII_TXD0") (class "Default")
      (node (ref "R6011") (pin "1") (pinfunction "1_1") (pintype "passive"))
    )
    (net (code "22") (name "/MCU_RGMII_TXD1") (class "Default")
      (node (ref "R6010") (pin "1") (pinfunction "1_1") (pintype "passive"))
    )
    (net (code "23") (name "/MCU_RGMII_TXD2") (class "Default")
      (node (ref "R6009") (pin "1") (pinfunction "1_1") (pintype "passive"))
    )
    (net (code "24") (name "/MCU_RGMII_TXD3") (class "Default")
      (node (ref "R6008") (pin "1") (pinfunction "1_1") (pintype "passive"))
    )
    (net (code "25") (name "/RESET_ETH_SW") (class "Default")
      (node (ref "U6000") (pin "101") (pinfunction "RESET_N_101") (pintype "input"))
    )
    (net (code "26") (name "/SWE") (class "Default")
      (node (ref "R6029") (pin "1") (pinfunction "1_1") (pintype "passive"))
      (node (ref "R6032") (pin "2") (pinfunction "2_2") (pintype "passive"))
      (node (ref "U6000") (pin "108") (pinfunction "SW_EN_108") (pintype "input"))
    )
    (net (code "27") (name "/TRXA1_N") (class "Default")
      (node (ref "J6000") (pin "10_1") (pinfunction "TRD1-_1_10_1") (pintype "passive"))
      (node (ref "U6000") (pin "2") (pinfunction "TXRX1M_A_2") (pintype "bidirectional"))
    )
    (net (code "28") (name "/TRXA1_P") (class "Default")
      (node (ref "J6000") (pin "11_1") (pinfunction "TRD1+_1_11_1") (pintype "passive"))
      (node (ref "U6000") (pin "1") (pinfunction "TXRX1P_A_1") (pintype "bidirectional"))
    )
    (net (code "29") (name "/TRXA2_N") (class "Default")
      (node (ref "J6000") (pin "10_2") (pinfunction "TRD1-_2_10_2") (pintype "passive"))
      (node (ref "U6000") (pin "13") (pinfunction "TXRX2M_A_13") (pintype "bidirectional"))
    )
    (net (code "30") (name "/TRXA2_P") (class "Default")
      (node (ref "J6000") (pin "11_2") (pinfunction "TRD1+_2_11_2") (pintype "passive"))
      (node (ref "U6000") (pin "12") (pinfunction "TXRX2P_A_12") (pintype "bidirectional"))
    )
    (net (code "31") (name "/TRXA3_N") (class "Default")
      (node (ref "J6000") (pin "10_3") (pinfunction "TRD1-_3_10_3") (pintype "passive"))
      (node (ref "U6000") (pin "25") (pinfunction "TXRX3M_A_25") (pintype "bidirectional"))
    )
    (net (code "32") (name "/TRXA3_P") (class "Default")
      (node (ref "J6000") (pin "11_3") (pinfunction "TRD1+_3_11_3") (pintype "passive"))
      (node (ref "U6000") (pin "24") (pinfunction "TXRX3P_A_24") (pintype "bidirectional"))
    )
    (net (code "33") (name "/TRXA4_N") (class "Default")
      (node (ref "J6000") (pin "10_4") (pinfunction "TRD1-_4_10_4") (pintype "passive"))
      (node (ref "U6000") (pin "41") (pinfunction "TXRX4M_A_41") (pintype "bidirectional"))
    )
    (net (code "34") (name "/TRXA4_P") (class "Default")
      (node (ref "J6000") (pin "11_4") (pinfunction "TRD1+_4_11_4") (pintype "passive"))
      (node (ref "U6000") (pin "40") (pinfunction "TXRX4P_A_40") (pintype "bidirectional"))
    )
    (net (code "35") (name "/TRXB1_N") (class "Default")
      (node (ref "J6000") (pin "5_1") (pinfunction "TRD2-_1_5_1") (pintype "passive"))
      (node (ref "U6000") (pin "5") (pinfunction "TXRX1M_B_5") (pintype "bidirectional"))
    )
    (net (code "36") (name "/TRXB1_P") (class "Default")
      (node (ref "J6000") (pin "4_1") (pinfunction "TRD2+_1_4_1") (pintype "passive"))
      (node (ref "U6000") (pin "4") (pinfunction "TXRX1P_B_4") (pintype "bidirectional"))
    )
    (net (code "37") (name "/TRXB2_N") (class "Default")
      (node (ref "J6000") (pin "5_2") (pinfunction "TRD2-_2_5_2") (pintype "passive"))
      (node (ref "U6000") (pin "16") (pinfunction "TXRX2M_B_16") (pintype "bidirectional"))
    )
    (net (code "38") (name "/TRXB2_P") (class "Default")
      (node (ref "J6000") (pin "4_2") (pinfunction "TRD2+_2_4_2") (pintype "passive"))
      (node (ref "U6000") (pin "15") (pinfunction "TXRX2P_B_15") (pintype "bidirectional"))
    )
    (net (code "39") (name "/TRXB3_N") (class "Default")
      (node (ref "J6000") (pin "5_3") (pinfunction "TRD2-_3_5_3") (pintype "passive"))
      (node (ref "U6000") (pin "27") (pinfunction "TXRX3M_B_27") (pintype "bidirectional"))
    )
    (net (code "40") (name "/TRXB3_P") (class "Default")
      (node (ref "J6000") (pin "4_3") (pinfunction "TRD2+_3_4_3") (pintype "passive"))
      (node (ref "U6000") (pin "26") (pinfunction "TXRX3P_B_26") (pintype "bidirectional"))
    )
    (net (code "41") (name "/TRXB4_N") (class "Default")
      (node (ref "J6000") (pin "5_4") (pinfunction "TRD2-_4_5_4") (pintype "passive"))
      (node (ref "U6000") (pin "44") (pinfunction "TXRX4M_B_44") (pintype "bidirectional"))
    )
    (net (code "42") (name "/TRXB4_P") (class "Default")
      (node (ref "J6000") (pin "4_4") (pinfunction "TRD2+_4_4_4") (pintype "passive"))
      (node (ref "U6000") (pin "43") (pinfunction "TXRX4P_B_43") (pintype "bidirectional"))
    )
    (net (code "43") (name "/TRXC1_N") (class "Default")
      (node (ref "J6000") (pin "2_1") (pinfunction "TRD3-_1_2_1") (pintype "passive"))
      (node (ref "U6000") (pin "7") (pinfunction "TXRX1M_C_7") (pintype "bidirectional"))
    )
    (net (code "44") (name "/TRXC1_P") (class "Default")
      (node (ref "J6000") (pin "3_1") (pinfunction "TRD3+_1_3_1") (pintype "passive"))
      (node (ref "U6000") (pin "6") (pinfunction "TXRX1P_C_6") (pintype "bidirectional"))
    )
    (net (code "45") (name "/TRXC2_N") (class "Default")
      (node (ref "J6000") (pin "2_2") (pinfunction "TRD3-_2_2_2") (pintype "passive"))
      (node (ref "U6000") (pin "18") (pinfunction "TXRX2M_C_18") (pintype "bidirectional"))
    )
    (net (code "46") (name "/TRXC2_P") (class "Default")
      (node (ref "J6000") (pin "3_2") (pinfunction "TRD3+_2_3_2") (pintype "passive"))
      (node (ref "U6000") (pin "17") (pinfunction "TXRX2P_C_17") (pintype "bidirectional"))
    )
    (net (code "47") (name "/TRXC3_N") (class "Default")
      (node (ref "J6000") (pin "2_3") (pinfunction "TRD3-_3_2_3") (pintype "passive"))
      (node (ref "U6000") (pin "29") (pinfunction "TXRX3M_C_29") (pintype "bidirectional"))
    )
    (net (code "48") (name "/TRXC3_P") (class "Default")
      (node (ref "J6000") (pin "3_3") (pinfunction "TRD3+_3_3_3") (pintype "passive"))
      (node (ref "U6000") (pin "28") (pinfunction "TXRX3P_C_28") (pintype "bidirectional"))
    )
    (net (code "49") (name "/TRXC4_N") (class "Default")
      (node (ref "J6000") (pin "2_4") (pinfunction "TRD3-_4_2_4") (pintype "passive"))
      (node (ref "U6000") (pin "46") (pinfunction "TXRX4M_C_46") (pintype "bidirectional"))
    )
    (net (code "50") (name "/TRXC4_P") (class "Default")
      (node (ref "J6000") (pin "3_4") (pinfunction "TRD3+_4_3_4") (pintype "passive"))
      (node (ref "U6000") (pin "45") (pinfunction "TXRX4P_C_45") (pintype "bidirectional"))
    )
    (net (code "51") (name "/TRXD1_N") (class "Default")
      (node (ref "J6000") (pin "9_1") (pinfunction "TRD4-_1_9_1") (pintype "passive"))
      (node (ref "U6000") (pin "9") (pinfunction "TXRX1M_D_9") (pintype "bidirectional"))
    )
    (net (code "52") (name "/TRXD1_P") (class "Default")
      (node (ref "J6000") (pin "8_1") (pinfunction "TRD4+_1_8_1") (pintype "passive"))
      (node (ref "U6000") (pin "8") (pinfunction "TXRX1P_D_8") (pintype "bidirectional"))
    )
    (net (code "53") (name "/TRXD2_N") (class "Default")
      (node (ref "J6000") (pin "9_2") (pinfunction "TRD4-_2_9_2") (pintype "passive"))
      (node (ref "U6000") (pin "21") (pinfunction "TXRX2M_D_21") (pintype "bidirectional"))
    )
    (net (code "54") (name "/TRXD2_P") (class "Default")
      (node (ref "J6000") (pin "8_2") (pinfunction "TRD4+_2_8_2") (pintype "passive"))
      (node (ref "U6000") (pin "20") (pinfunction "TXRX2P_D_20") (pintype "bidirectional"))
    )
    (net (code "55") (name "/TRXD3_N") (class "Default")
      (node (ref "J6000") (pin "9_3") (pinfunction "TRD4-_3_9_3") (pintype "passive"))
      (node (ref "U6000") (pin "32") (pinfunction "TXRX3M_D_32") (pintype "bidirectional"))
    )
    (net (code "56") (name "/TRXD3_P") (class "Default")
      (node (ref "J6000") (pin "8_3") (pinfunction "TRD4+_3_8_3") (pintype "passive"))
      (node (ref "U6000") (pin "31") (pinfunction "TXRX3P_D_31") (pintype "bidirectional"))
    )
    (net (code "57") (name "/TRXD4_N") (class "Default")
      (node (ref "J6000") (pin "9_4") (pinfunction "TRD4-_4_9_4") (pintype "passive"))
      (node (ref "U6000") (pin "49") (pinfunction "TXRX4M_D_49") (pintype "bidirectional"))
    )
    (net (code "58") (name "/TRXD4_P") (class "Default")
      (node (ref "J6000") (pin "8_4") (pinfunction "TRD4+_4_8_4") (pintype "passive"))
      (node (ref "U6000") (pin "48") (pinfunction "TXRX4P_D_48") (pintype "bidirectional"))
    )
    (net (code "59") (name "GND") (class "Default")
      (node (ref "C6000") (pin "2") (pinfunction "2_2") (pintype "passive"))
      (node (ref "C6001") (pin "2") (pinfunction "2_2") (pintype "passive"))
      (node (ref "C6002") (pin "2") (pinfunction "2_2") (pintype "passive"))
      (node (ref "C6003") (pin "2") (pinfunction "2_2") (pintype "passive"))
      (node (ref "C6004") (pin "2") (pinfunction "2_2") (pintype "passive"))
      (node (ref "C6005") (pin "2") (pinfunction "2_2") (pintype "passive"))
      (node (ref "C6006") (pin "2") (pinfunction "2_2") (pintype "passive"))
      (node (ref "C6007") (pin "2") (pinfunction "2_2") (pintype "passive"))
      (node (ref "C6008") (pin "1") (pinfunction "1_1") (pintype "passive"))
      (node (ref "C6009") (pin "2") (pinfunction "2_2") (pintype "passive"))
      (node (ref "C6010") (pin "2") (pinfunction "2_2") (pintype "passive"))
      (node (ref "C6011") (pin "2") (pinfunction "2_2") (pintype "passive"))
      (node (ref "C6012") (pin "2") (pinfunction "2_2") (pintype "passive"))
      (node (ref "C6013") (pin "2") (pinfunction "2_2") (pintype "passive"))
      (node (ref "C6014") (pin "2") (pinfunction "2_2") (pintype "passive"))
      (node (ref "C6015") (pin "2") (pinfunction "2_2") (pintype "passive"))
      (node (ref "C6016") (pin "2") (pinfunction "2_2") (pintype "passive"))
      (node (ref "C6017") (pin "2") (pinfunction "2_2") (pintype "passive"))
      (node (ref "C6018") (pin "2") (pinfunction "2_2") (pintype "passive"))
      (node (ref "C6019") (pin "2") (pinfunction "2_2") (pintype "passive"))
      (node (ref "C6020") (pin "2") (pinfunction "2_2") (pintype "passive"))
      (node (ref "C6021") (pin "2") (pinfunction "2_2") (pintype "passive"))
      (node (ref "C6022") (pin "2") (pinfunction "2_2") (pintype "passive"))
      (node (ref "C6023") (pin "2") (pinfunction "2_2") (pintype "passive"))
      (node (ref "C6024") (pin "2") (pinfunction "2_2") (pintype "passive"))
      (node (ref "C6025") (pin "2") (pinfunction "2_2") (pintype "passive"))
      (node (ref "C6026") (pin "2") (pinfunction "2_2") (pintype "passive"))
      (node (ref "C6027") (pin "2") (pinfunction "2_2") (pintype "passive"))
      (node (ref "C6028") (pin "2") (pinfunction "2_2") (pintype "passive"))
      (node (ref "C6029") (pin "2") (pinfunction "2_2") (pintype "passive"))
      (node (ref "C6030") (pin "2") (pinfunction "2_2") (pintype "passive"))
      (node (ref "C6031") (pin "2") (pinfunction "2_2") (pintype "passive"))
      (node (ref "C6032") (pin "2") (pinfunction "2_2") (pintype "passive"))
      (node (ref "C6033") (pin "2") (pinfunction "2_2") (pintype "passive"))
      (node (ref "C6034") (pin "2") (pinfunction "2_2") (pintype "passive"))
      (node (ref "C6035") (pin "2") (pinfunction "2_2") (pintype "passive"))
      (node (ref "C6036") (pin "2") (pinfunction "2_2") (pintype "passive"))
      (node (ref "C6037") (pin "2") (pinfunction "2_2") (pintype "passive"))
      (node (ref "C6038") (pin "2") (pinfunction "2_2") (pintype "passive"))
      (node (ref "C6039") (pin "2") (pinfunction "2_2") (pintype "passive"))
      (node (ref "C6040") (pin "2") (pinfunction "2_2") (pintype "passive"))
      (node (ref "C6041") (pin "2") (pinfunction "2_2") (pintype "passive"))
      (node (ref "C6042") (pin "2") (pinfunction "2_2") (pintype "passive"))
      (node (ref "C6043") (pin "2") (pinfunction "2_2") (pintype "passive"))
      (node (ref "C6044") (pin "2") (pinfunction "2_2") (pintype "passive"))
      (node (ref "C6045") (pin "2") (pinfunction "2_2") (pintype "passive"))
      (node (ref "C6046") (pin "2") (pinfunction "2_2") (pintype "passive"))
      (node (ref "C6047") (pin "2") (pinfunction "2_2") (pintype "passive"))
      (node (ref "C6048") (pin "2") (pinfunction "2_2") (pintype "passive"))
      (node (ref "C6049") (pin "2") (pinfunction "2_2") (pintype "passive"))
      (node (ref "C6050") (pin "2") (pinfunction "2_2") (pintype "passive"))
      (node (ref "C6051") (pin "2") (pinfunction "2_2") (pintype "passive"))
      (node (ref "C6052") (pin "2") (pinfunction "2_2") (pintype "passive"))
      (node (ref "C6053") (pin "2") (pinfunction "2_2") (pintype "passive"))
      (node (ref "C6054") (pin "2") (pinfunction "2_2") (pintype "passive"))
      (node (ref "C6055") (pin "2") (pinfunction "2_2") (pintype "passive"))
      (node (ref "C6056") (pin "2") (pinfunction "2_2") (pintype "passive"))
      (node (ref "C6057") (pin "2") (pinfunction "2_2") (pintype "passive"))
      (node (ref "C6058") (pin "2") (pinfunction "2_2") (pintype "passive"))
      (node (ref "C6059") (pin "2") (pinfunction "2_2") (pintype "passive"))
      (node (ref "C6060") (pin "2") (pinfunction "2_2") (pintype "passive"))
      (node (ref "C6061") (pin "2") (pinfunction "2_2") (pintype "passive"))
      (node (ref "C6062") (pin "2") (pinfunction "2_2") (pintype "passive"))
      (node (ref "C6063") (pin "2") (pinfunction "2_2") (pintype "passive"))
      (node (ref "C6064") (pin "2") (pinfunction "2_2") (pintype "passive"))
      (node (ref "C6065") (pin "2") (pinfunction "2_2") (pintype "passive"))
      (node (ref "R6016") (pin "2") (pinfunction "2_2") (pintype "passive"))
      (node (ref "R6018") (pin "1") (pinfunction "1_1") (pintype "passive"))
      (node (ref "R6022") (pin "1") (pinfunction "1_1") (pintype "passive"))
      (node (ref "R6023") (pin "1") (pinfunction "1_1") (pintype "passive"))
      (node (ref "R6025") (pin "2") (pinfunction "2_2") (pintype "passive"))
      (node (ref "R6031") (pin "1") (pinfunction "1_1") (pintype "passive"))
      (node (ref "R6032") (pin "1") (pinfunction "1_1") (pintype "passive"))
      (node (ref "U6000") (pin "112") (pinfunction "GND_112") (pintype "power_in"))
      (node (ref "U6000") (pin "116") (pinfunction "GND_116") (pintype "power_in"))
      (node (ref "U6000") (pin "120") (pinfunction "GND_120") (pintype "power_in"))
      (node (ref "U6000") (pin "121") (pinfunction "GND_121") (pintype "power_in"))
      (node (ref "U6000") (pin "126") (pinfunction "GND_126") (pintype "power_in"))
      (node (ref "U6000") (pin "133") (pinfunction "ePAD_133") (pintype "power_in"))
      (node (ref "U6000") (pin "36") (pinfunction "GND_36") (pintype "power_in"))
      (node (ref "U6000") (pin "37") (pinfunction "GND_37") (pintype "power_in"))
      (node (ref "U6000") (pin "72") (pinfunction "GND_72") (pintype "power_in"))
      (node (ref "U6000") (pin "73") (pinfunction "GND_73") (pintype "power_in"))
      (node (ref "Y6000") (pin "2") (pinfunction "GND_2") (pintype "passive"))
      (node (ref "Y6000") (pin "4") (pinfunction "GND_4") (pintype "passive"))
    )
    (net (code "60") (name "Net-(C6008-Pad2)") (class "Default")
      (node (ref "C6008") (pin "2") (pinfunction "2_2") (pintype "passive"))
      (node (ref "J6000") (pin "S1") (pinfunction "SHIELD_S1") (pintype "passive"))
      (node (ref "J6000") (pin "S2") (pinfunction "SHIELD_S2") (pintype "passive"))
      (node (ref "J6000") (pin "S3") (pinfunction "SHIELD_S3") (pintype "passive"))
      (node (ref "J6000") (pin "S4") (pinfunction "SHIELD_S4") (pintype "passive"))
      (node (ref "R6016") (pin "1") (pinfunction "1_1") (pintype "passive"))
    )
    (net (code "61") (name "Net-(C6016-Pad1)") (class "Default")
      (node (ref "C6016") (pin "1") (pinfunction "1_1") (pintype "passive"))
      (node (ref "C6017") (pin "1") (pinfunction "1_1") (pintype "passive"))
      (node (ref "C6018") (pin "1") (pinfunction "1_1") (pintype "passive"))
      (node (ref "C6019") (pin "1") (pinfunction "1_1") (pintype "passive"))
      (node (ref "C6020") (pin "1") (pinfunction "1_1") (pintype "passive"))
      (node (ref "C6021") (pin "1") (pinfunction "1_1") (pintype "passive"))
      (node (ref "C6022") (pin "1") (pinfunction "1_1") (pintype "passive"))
      (node (ref "C6023") (pin "1") (pinfunction "1_1") (pintype "passive"))
      (node (ref "C6024") (pin "1") (pinfunction "1_1") (pintype "passive"))
      (node (ref "C6029") (pin "1") (pinfunction "1_1") (pintype "passive"))
      (node (ref "FB6001") (pin "1") (pinfunction "1_1") (pintype "passive"))
      (node (ref "U6000") (pin "118") (pinfunction "AVDDL_118") (pintype "power_in"))
      (node (ref "U6000") (pin "123") (pinfunction "AVDDL_123") (pintype "power_in"))
      (node (ref "U6000") (pin "127") (pinfunction "AVDDL_127") (pintype "power_in"))
      (node (ref "U6000") (pin "14") (pinfunction "AVDDL_14") (pintype "power_in"))
      (node (ref "U6000") (pin "19") (pinfunction "AVDDL_19") (pintype "power_in"))
      (node (ref "U6000") (pin "3") (pinfunction "AVDDL_3") (pintype "power_in"))
      (node (ref "U6000") (pin "30") (pinfunction "AVDDL_30") (pintype "power_in"))
      (node (ref "U6000") (pin "42") (pinfunction "AVDDL_42") (pintype "power_in"))
      (node (ref "U6000") (pin "47") (pinfunction "AVDDL_47") (pintype "power_in"))
    )
    (net (code "62") (name "Net-(C6025-Pad1)") (class "Default")
      (node (ref "C6025") (pin "1") (pinfunction "1_1") (pintype "passive"))
      (node (ref "C6026") (pin "1") (pinfunction "1_1") (pintype "passive"))
      (node (ref "C6027") (pin "1") (pinfunction "1_1") (pintype "passive"))
      (node (ref "C6028") (pin "1") (pinfunction "1_1") (pintype "passive"))
      (node (ref "FB6000") (pin "2") (pinfunction "2_2") (pintype "passive"))
      (node (ref "U6000") (pin "104") (pinfunction "VDDIO_104") (pintype "power_in"))
      (node (ref "U6000") (pin "65") (pinfunction "VDDIO_65") (pintype "power_in"))
      (node (ref "U6000") (pin "76") (pinfunction "VDDIO_76") (pintype "power_in"))
    )
    (net (code "63") (name "Net-(C6030-Pad1)") (class "Default")
      (node (ref "C6030") (pin "1") (pinfunction "1_1") (pintype "passive"))
      (node (ref "C6031") (pin "1") (pinfunction "1_1") (pintype "passive"))
      (node (ref "C6032") (pin "1") (pinfunction "1_1") (pintype "passive"))
      (node (ref "C6033") (pin "1") (pinfunction "1_1") (pintype "passive"))
      (node (ref "C6034") (pin "1") (pinfunction "1_1") (pintype "passive"))
      (node (ref "C6035") (pin "1") (pinfunction "1_1") (pintype "passive"))
      (node (ref "C6036") (pin "1") (pinfunction "1_1") (pintype "passive"))
      (node (ref "C6037") (pin "1") (pinfunction "1_1") (pintype "passive"))
      (node (ref "FB6002") (pin "1") (pinfunction "1_1") (pintype "passive"))
      (node (ref "U6000") (pin "10") (pinfunction "AVDDH_10") (pintype "power_in"))
      (node (ref "U6000") (pin "115") (pinfunction "AVDDH_115") (pintype "power_in"))
      (node (ref "U6000") (pin "125") (pinfunction "AVDDH_125") (pintype "power_in"))
      (node (ref "U6000") (pin "132") (pinfunction "AVDDH_132") (pintype "power_in"))
      (node (ref "U6000") (pin "22") (pinfunction "AVDDH_22") (pintype "power_in"))
      (node (ref "U6000") (pin "35") (pinfunction "AVDDH_35") (pintype "power_in"))
      (node (ref "U6000") (pin "50") (pinfunction "AVDDH_50") (pintype "power_in"))
    )
    (net (code "64") (name "Net-(C6038-Pad1)") (class "Default")
      (node (ref "C6038") (pin "1") (pinfunction "1_1") (pintype "passive"))
      (node (ref "C6039") (pin "1") (pinfunction "1_1") (pintype "passive"))
      (node (ref "C6040") (pin "1") (pinfunction "1_1") (pintype "passive"))
      (node (ref "C6041") (pin "1") (pinfunction "1_1") (pintype "passive"))
      (node (ref "C6042") (pin "1") (pinfunction "1_1") (pintype "passive"))
      (node (ref "C6043") (pin "1") (pinfunction "1_1") (pintype "passive"))
      (node (ref "C6044") (pin "1") (pinfunction "1_1") (pintype "passive"))
      (node (ref "C6045") (pin "1") (pinfunction "1_1") (pintype "passive"))
      (node (ref "C6046") (pin "1") (pinfunction "1_1") (pintype "passive"))
      (node (ref "C6047") (pin "1") (pinfunction "1_1") (pintype "passive"))
      (node (ref "C6048") (pin "1") (pinfunction "1_1") (pintype "passive"))
      (node (ref "C6049") (pin "1") (pinfunction "1_1") (pintype "passive"))
      (node (ref "C6050") (pin "1") (pinfunction "1_1") (pintype "passive"))
      (node (ref "FB6003") (pin "1") (pinfunction "1_1") (pintype "passive"))
      (node (ref "U6000") (pin "109") (pinfunction "DVDDL_109") (pintype "power_in"))
      (node (ref "U6000") (pin "11") (pinfunction "DVDDL_11") (pintype "power_in"))
      (node (ref "U6000") (pin "114") (pinfunction "DVDDL_114") (pintype "power_in"))
      (node (ref "U6000") (pin "23") (pinfunction "DVDDL_23") (pintype "power_in"))
      (node (ref "U6000") (pin "51") (pinfunction "DVDDL_51") (pintype "power_in"))
      (node (ref "U6000") (pin "60") (pinfunction "DVDDL_60") (pintype "power_in"))
      (node (ref "U6000") (pin "70") (pinfunction "DVDDL_70") (pintype "power_in"))
      (node (ref "U6000") (pin "71") (pinfunction "DVDDL_71") (pintype "power_in"))
      (node (ref "U6000") (pin "74") (pinfunction "DVDDL_74") (pintype "power_in"))
      (node (ref "U6000") (pin "77") (pinfunction "DVDDL_77") (pintype "power_in"))
      (node (ref "U6000") (pin "91") (pinfunction "DVDDL_91") (pintype "power_in"))
      (node (ref "U6000") (pin "95") (pinfunction "DVDDL_95") (pintype "power_in"))
    )
    (net (code "65") (name "Net-(C6055-Pad1)") (class "Default")
      (node (ref "C6055") (pin "1") (pinfunction "1_1") (pintype "passive"))
      (node (ref "C6056") (pin "1") (pinfunction "1_1") (pintype "passive"))
      (node (ref "C6057") (pin "1") (pinfunction "1_1") (pintype "passive"))
      (node (ref "FB6004") (pin "1") (pinfunction "1_1") (pintype "passive"))
      (node (ref "U6000") (pin "78") (pinfunction "VDDLS_78") (pintype "power_in"))
      (node (ref "U6000") (pin "88") (pinfunction "VDDLS_88") (pintype "power_in"))
    )
    (net (code "66") (name "Net-(C6058-Pad1)") (class "Default")
      (node (ref "C6058") (pin "1") (pinfunction "1_1") (pintype "passive"))
      (node (ref "C6059") (pin "1") (pinfunction "1_1") (pintype "passive"))
      (node (ref "C6060") (pin "1") (pinfunction "1_1") (pintype "passive"))
      (node (ref "FB6005") (pin "1") (pinfunction "1_1") (pintype "passive"))
      (node (ref "U6000") (pin "79") (pinfunction "VDDHS_79") (pintype "power_in"))
      (node (ref "U6000") (pin "87") (pinfunction "VDDHS_87") (pintype "power_in"))
    )
    (net (code "67") (name "Net-(J6000-Pad14_1)") (class "Default")
      (node (ref "J6000") (pin "14_1") (pinfunction "14_1_14_1") (pintype "passive"))
      (node (ref "R6013") (pin "1") (pinfunction "1_1") (pintype "passive"))
    )
    (net (code "68") (name "Net-(J6000-Pad14_2)") (class "Default")
      (node (ref "J6000") (pin "14_2") (pinfunction "14_2_14_2") (pintype "passive"))
      (node (ref "R6012") (pin "1") (pinfunction "1_1") (pintype "passive"))
    )
    (net (code "69") (name "Net-(J6000-Pad14_3)") (class "Default")
      (node (ref "J6000") (pin "14_3") (pinfunction "14_3_14_3") (pintype "passive"))
      (node (ref "R6024") (pin "1") (pinfunction "1_1") (pintype "passive"))
    )
    (net (code "70") (name "Net-(J6000-Pad14_4)") (class "Default")
      (node (ref "J6000") (pin "14_4") (pinfunction "14_4_14_4") (pintype "passive"))
      (node (ref "R6027") (pin "1") (pinfunction "1_1") (pintype "passive"))
    )
    (net (code "71") (name "Net-(J6000-Pad15_1)") (class "Default")
      (node (ref "J6000") (pin "15_1") (pinfunction "15_1_15_1") (pintype "passive"))
      (node (ref "R6015") (pin "1") (pinfunction "1_1") (pintype "passive"))
    )
    (net (code "72") (name "Net-(J6000-Pad15_2)") (class "Default")
      (node (ref "J6000") (pin "15_2") (pinfunction "15_2_15_2") (pintype "passive"))
      (node (ref "R6014") (pin "1") (pinfunction "1_1") (pintype "passive"))
    )
    (net (code "73") (name "Net-(J6000-Pad15_3)") (class "Default")
      (node (ref "J6000") (pin "15_3") (pinfunction "15_3_15_3") (pintype "passive"))
      (node (ref "R6026") (pin "1") (pinfunction "1_1") (pintype "passive"))
    )
    (net (code "74") (name "Net-(J6000-Pad15_4)") (class "Default")
      (node (ref "J6000") (pin "15_4") (pinfunction "15_4_15_4") (pintype "passive"))
      (node (ref "R6030") (pin "1") (pinfunction "1_1") (pintype "passive"))
    )
    (net (code "75") (name "Net-(J6000A-TRCT1_1)") (class "Default")
      (node (ref "C6004") (pin "1") (pinfunction "1_1") (pintype "passive"))
      (node (ref "J6000") (pin "12_1") (pinfunction "TRCT1_1_12_1") (pintype "passive"))
    )
    (net (code "76") (name "Net-(J6000A-TRCT2_1)") (class "Default")
      (node (ref "C6005") (pin "1") (pinfunction "1_1") (pintype "passive"))
      (node (ref "J6000") (pin "6_1") (pinfunction "TRCT2_1_6_1") (pintype "passive"))
    )
    (net (code "77") (name "Net-(J6000A-TRCT3_1)") (class "Default")
      (node (ref "C6006") (pin "1") (pinfunction "1_1") (pintype "passive"))
      (node (ref "J6000") (pin "1_1") (pinfunction "TRCT3_1_1_1") (pintype "passive"))
    )
    (net (code "78") (name "Net-(J6000A-TRCT4_1)") (class "Default")
      (node (ref "C6007") (pin "1") (pinfunction "1_1") (pintype "passive"))
      (node (ref "J6000") (pin "7_1") (pinfunction "TRCT4_1_7_1") (pintype "passive"))
    )
    (net (code "79") (name "Net-(J6000B-TRCT1_2)") (class "Default")
      (node (ref "C6000") (pin "1") (pinfunction "1_1") (pintype "passive"))
      (node (ref "J6000") (pin "12_2") (pinfunction "TRCT1_2_12_2") (pintype "passive"))
    )
    (net (code "80") (name "Net-(J6000B-TRCT2_2)") (class "Default")
      (node (ref "C6001") (pin "1") (pinfunction "1_1") (pintype "passive"))
      (node (ref "J6000") (pin "6_2") (pinfunction "TRCT2_2_6_2") (pintype "passive"))
    )
    (net (code "81") (name "Net-(J6000B-TRCT3_2)") (class "Default")
      (node (ref "C6002") (pin "1") (pinfunction "1_1") (pintype "passive"))
      (node (ref "J6000") (pin "1_2") (pinfunction "TRCT3_2_1_2") (pintype "passive"))
    )
    (net (code "82") (name "Net-(J6000B-TRCT4_2)") (class "Default")
      (node (ref "C6003") (pin "1") (pinfunction "1_1") (pintype "passive"))
      (node (ref "J6000") (pin "7_2") (pinfunction "TRCT4_2_7_2") (pintype "passive"))
    )
    (net (code "83") (name "Net-(J6000C-TRCT1_3)") (class "Default")
      (node (ref "C6012") (pin "1") (pinfunction "1_1") (pintype "passive"))
      (node (ref "J6000") (pin "12_3") (pinfunction "TRCT1_3_12_3") (pintype "passive"))
    )
    (net (code "84") (name "Net-(J6000C-TRCT2_3)") (class "Default")
      (node (ref "C6013") (pin "1") (pinfunction "1_1") (pintype "passive"))
      (node (ref "J6000") (pin "6_3") (pinfunction "TRCT2_3_6_3") (pintype "passive"))
    )
    (net (code "85") (name "Net-(J6000C-TRCT3_3)") (class "Default")
      (node (ref "C6014") (pin "1") (pinfunction "1_1") (pintype "passive"))
      (node (ref "J6000") (pin "1_3") (pinfunction "TRCT3_3_1_3") (pintype "passive"))
    )
    (net (code "86") (name "Net-(J6000C-TRCT4_3)") (class "Default")
      (node (ref "C6015") (pin "1") (pinfunction "1_1") (pintype "passive"))
      (node (ref "J6000") (pin "7_3") (pinfunction "TRCT4_3_7_3") (pintype "passive"))
    )
    (net (code "87") (name "Net-(J6000D-TRCT1_4)") (class "Default")
      (node (ref "C6051") (pin "1") (pinfunction "1_1") (pintype "passive"))
      (node (ref "J6000") (pin "12_4") (pinfunction "TRCT1_4_12_4") (pintype "passive"))
    )
    (net (code "88") (name "Net-(J6000D-TRCT2_4)") (class "Default")
      (node (ref "C6052") (pin "1") (pinfunction "1_1") (pintype "passive"))
      (node (ref "J6000") (pin "6_4") (pinfunction "TRCT2_4_6_4") (pintype "passive"))
    )
    (net (code "89") (name "Net-(J6000D-TRCT3_4)") (class "Default")
      (node (ref "C6053") (pin "1") (pinfunction "1_1") (pintype "passive"))
      (node (ref "J6000") (pin "1_4") (pinfunction "TRCT3_4_1_4") (pintype "passive"))
    )
    (net (code "90") (name "Net-(J6000D-TRCT4_4)") (class "Default")
      (node (ref "C6054") (pin "1") (pinfunction "1_1") (pintype "passive"))
      (node (ref "J6000") (pin "7_4") (pinfunction "TRCT4_4_7_4") (pintype "passive"))
    )
    (net (code "91") (name "Net-(U6000A-ISET)") (class "Default")
      (node (ref "R6025") (pin "1") (pinfunction "1_1") (pintype "passive"))
      (node (ref "U6000") (pin "130") (pinfunction "ISET_130") (pintype "passive"))
    )
    (net (code "92") (name "Net-(U6000A-RXD6_0)") (class "Default")
      (node (ref "R6011") (pin "2") (pinfunction "2_2") (pintype "passive"))
      (node (ref "U6000") (pin "69") (pinfunction "RXD6_0_69") (pintype "bidirectional"))
    )
    (net (code "93") (name "Net-(U6000A-RXD6_1)") (class "Default")
      (node (ref "R6010") (pin "2") (pinfunction "2_2") (pintype "passive"))
      (node (ref "U6000") (pin "68") (pinfunction "RXD6_1_68") (pintype "bidirectional"))
    )
    (net (code "94") (name "Net-(U6000A-RXD6_2)") (class "Default")
      (node (ref "R6009") (pin "2") (pinfunction "2_2") (pintype "passive"))
      (node (ref "U6000") (pin "67") (pinfunction "RXD6_2_67") (pintype "bidirectional"))
    )
    (net (code "95") (name "Net-(U6000A-RXD6_3)") (class "Default")
      (node (ref "R6008") (pin "2") (pinfunction "2_2") (pintype "passive"))
      (node (ref "U6000") (pin "66") (pinfunction "RXD6_3_66") (pintype "bidirectional"))
    )
    (net (code "96") (name "Net-(U6000A-RX_CLK6{slash}REFCLKO6)") (class "Default")
      (node (ref "R6006") (pin "2") (pinfunction "2_2") (pintype "passive"))
      (node (ref "U6000") (pin "61") (pinfunction "RX_CLK6/REFCLKO6_61") (pintype "bidirectional"))
    )
    (net (code "97") (name "Net-(U6000A-RX_DV6{slash}CRS_DV6{slash}RX_CTL6)") (class "Default")
      (node (ref "R6007") (pin "2") (pinfunction "2_2") (pintype "passive"))
      (node (ref "U6000") (pin "62") (pinfunction "RX_DV6/CRS_DV6/RX_CTL6_62") (pintype "bidirectional"))
    )
    (net (code "98") (name "Net-(U6000A-SCL{slash}MDC)") (class "Default")
      (node (ref "R6021") (pin "2") (pinfunction "2_2") (pintype "passive"))
      (node (ref "U6000") (pin "106") (pinfunction "SCL/MDC_106") (pintype "input"))
    )
    (net (code "99") (name "Net-(U6000A-SDI{slash}SDA{slash}MDIO)") (class "Default")
      (node (ref "R6020") (pin "2") (pinfunction "2_2") (pintype "passive"))
      (node (ref "U6000") (pin "103") (pinfunction "SDI/SDA/MDIO_103") (pintype "bidirectional"))
    )
    (net (code "100") (name "Net-(U6000A-SYNCLKO)") (class "Default")
      (node (ref "TP6000") (pin "1") (pinfunction "1_1") (pintype "passive"))
      (node (ref "U6000") (pin "100") (pinfunction "SYNCLKO_100") (pintype "bidirectional"))
    )
    (net (code "101") (name "Net-(U6000A-S_REXT)") (class "Default")
      (node (ref "R6018") (pin "2") (pinfunction "2_2") (pintype "passive"))
      (node (ref "U6000") (pin "82") (pinfunction "S_REXT_82") (pintype "passive"))
    )
    (net (code "102") (name "Net-(U6000A-TXD6_0)") (class "Default")
      (node (ref "R6005") (pin "2") (pinfunction "2_2") (pintype "passive"))
      (node (ref "U6000") (pin "59") (pinfunction "TXD6_0_59") (pintype "input"))
    )
    (net (code "103") (name "Net-(U6000A-TXD6_1)") (class "Default")
      (node (ref "R6004") (pin "2") (pinfunction "2_2") (pintype "passive"))
      (node (ref "U6000") (pin "58") (pinfunction "TXD6_1_58") (pintype "input"))
    )
    (net (code "104") (name "Net-(U6000A-TXD6_2)") (class "Default")
      (node (ref "R6003") (pin "2") (pinfunction "2_2") (pintype "passive"))
      (node (ref "U6000") (pin "57") (pinfunction "TXD6_2_57") (pintype "input"))
    )
    (net (code "105") (name "Net-(U6000A-TXD6_3)") (class "Default")
      (node (ref "R6002") (pin "2") (pinfunction "2_2") (pintype "passive"))
      (node (ref "U6000") (pin "56") (pinfunction "TXD6_3_56") (pintype "input"))
    )
    (net (code "106") (name "Net-(U6000A-TX_CLK6{slash}REFCLKI6)") (class "Default")
      (node (ref "R6000") (pin "2") (pinfunction "2_2") (pintype "passive"))
      (node (ref "U6000") (pin "52") (pinfunction "TX_CLK6/REFCLKI6_52") (pintype "bidirectional"))
    )
    (net (code "107") (name "Net-(U6000A-TX_EN6{slash}TX_CTL6)") (class "Default")
      (node (ref "R6001") (pin "2") (pinfunction "2_2") (pintype "passive"))
      (node (ref "U6000") (pin "53") (pinfunction "TX_EN6/TX_CTL6_53") (pintype "input"))
    )
    (net (code "108") (name "Net-(U6000A-XI)") (class "Default")
      (node (ref "C6011") (pin "1") (pinfunction "1_1") (pintype "passive"))
      (node (ref "U6000") (pin "129") (pinfunction "XI_129") (pintype "input"))
      (node (ref "Y6000") (pin "3") (pinfunction "OSC2_3") (pintype "passive"))
    )
    (net (code "109") (name "Net-(U6000A-XO)") (class "Default")
      (node (ref "C6010") (pin "1") (pinfunction "1_1") (pintype "passive"))
      (node (ref "U6000") (pin "128") (pinfunction "XO_128") (pintype "output"))
      (node (ref "Y6000") (pin "1") (pinfunction "OSC1_1") (pintype "passive"))
    )
    (net (code "110") (name "VDD_HV_B") (class "Default")
      (node (ref "C6009") (pin "1") (pinfunction "1_1") (pintype "passive"))
      (node (ref "FB6000") (pin "1") (pinfunction "1_1") (pintype "passive"))
      (node (ref "R6012") (pin "2") (pinfunction "2_2") (pintype "passive"))
      (node (ref "R6013") (pin "2") (pinfunction "2_2") (pintype "passive"))
      (node (ref "R6014") (pin "2") (pinfunction "2_2") (pintype "passive"))
      (node (ref "R6015") (pin "2") (pinfunction "2_2") (pintype "passive"))
      (node (ref "R6017") (pin "2") (pinfunction "2_2") (pintype "passive"))
      (node (ref "R6019") (pin "2") (pinfunction "2_2") (pintype "passive"))
      (node (ref "R6024") (pin "2") (pinfunction "2_2") (pintype "passive"))
      (node (ref "R6026") (pin "2") (pinfunction "2_2") (pintype "passive"))
      (node (ref "R6027") (pin "2") (pinfunction "2_2") (pintype "passive"))
      (node (ref "R6028") (pin "2") (pinfunction "2_2") (pintype "passive"))
      (node (ref "R6029") (pin "2") (pinfunction "2_2") (pintype "passive"))
      (node (ref "R6030") (pin "2") (pinfunction "2_2") (pintype "passive"))
    )
    (net (code "111") (name "VREG_1P2") (class "Default")
      (node (ref "C6061") (pin "1") (pinfunction "1_1") (pintype "passive"))
      (node (ref "C6063") (pin "1") (pinfunction "1_1") (pintype "passive"))
      (node (ref "C6064") (pin "1") (pinfunction "1_1") (pintype "passive"))
      (node (ref "FB6001") (pin "2") (pinfunction "2_2") (pintype "passive"))
      (node (ref "FB6003") (pin "2") (pinfunction "2_2") (pintype "passive"))
      (node (ref "FB6004") (pin "2") (pinfunction "2_2") (pintype "passive"))
    )
    (net (code "112") (name "VREG_2P5") (class "Default")
      (node (ref "C6062") (pin "1") (pinfunction "1_1") (pintype "passive"))
      (node (ref "C6065") (pin "1") (pinfunction "1_1") (pintype "passive"))
      (node (ref "FB6002") (pin "2") (pinfunction "2_2") (pintype "passive"))
      (node (ref "FB6005") (pin "2") (pinfunction "2_2") (pintype "passive"))
    )
    (net (code "113") (name "unconnected-(U6000A-COL6-Pad55)") (class "Default")
      (node (ref "U6000") (pin "55") (pinfunction "COL6_55") (pintype "bidirectional"))
    )
    (net (code "114") (name "unconnected-(U6000A-CRS6-Pad64)") (class "Default")
      (node (ref "U6000") (pin "64") (pinfunction "CRS6_64") (pintype "bidirectional"))
    )
    (net (code "115") (name "unconnected-(U6000A-GPIO_1-Pad94)") (class "Default")
      (node (ref "U6000") (pin "94") (pinfunction "GPIO_1_94") (pintype "bidirectional"))
    )
    (net (code "116") (name "unconnected-(U6000A-PME_N-Pad98)") (class "Default")
      (node (ref "U6000") (pin "98") (pinfunction "PME_N_98") (pintype "output"))
    )
    (net (code "117") (name "unconnected-(U6000A-RX_ER6-Pad63)") (class "Default")
      (node (ref "U6000") (pin "63") (pinfunction "RX_ER6_63") (pintype "bidirectional"))
    )
    (net (code "118") (name "unconnected-(U6000A-SCS_N-Pad105)") (class "Default")
      (node (ref "U6000") (pin "105") (pinfunction "SCS_N_105") (pintype "input"))
    )
    (net (code "119") (name "unconnected-(U6000A-SDO-Pad102)") (class "Default")
      (node (ref "U6000") (pin "102") (pinfunction "SDO_102") (pintype "output"))
    )
    (net (code "120") (name "unconnected-(U6000A-S_IN7M-Pad83)") (class "Default")
      (node (ref "U6000") (pin "83") (pinfunction "S_IN7M_83") (pintype "input"))
    )
    (net (code "121") (name "unconnected-(U6000A-S_IN7P-Pad84)") (class "Default")
      (node (ref "U6000") (pin "84") (pinfunction "S_IN7P_84") (pintype "input"))
    )
    (net (code "122") (name "unconnected-(U6000A-S_OUT7M-Pad86)") (class "Default")
      (node (ref "U6000") (pin "86") (pinfunction "S_OUT7M_86") (pintype "output"))
    )
    (net (code "123") (name "unconnected-(U6000A-S_OUT7P-Pad85)") (class "Default")
      (node (ref "U6000") (pin "85") (pinfunction "S_OUT7P_85") (pintype "output"))
    )
    (net (code "124") (name "unconnected-(U6000A-TX_ER6-Pad54)") (class "Default")
      (node (ref "U6000") (pin "54") (pinfunction "TX_ER6_54") (pintype "input"))
    )
    (net (code "125") (name "unconnected-(U6000B-NC_33-Pad33)") (class "Default")
      (node (ref "U6000") (pin "33") (pinfunction "NC_33_33") (pintype "passive"))
    )
    (net (code "126") (name "unconnected-(U6000B-NC_34-Pad34)") (class "Default")
      (node (ref "U6000") (pin "34") (pinfunction "NC_34_34") (pintype "passive"))
    )
    (net (code "127") (name "unconnected-(U6000B-NC_38-Pad38)") (class "Default")
      (node (ref "U6000") (pin "38") (pinfunction "NC_38_38") (pintype "passive"))
    )
    (net (code "128") (name "unconnected-(U6000B-NC_39-Pad39)") (class "Default")
      (node (ref "U6000") (pin "39") (pinfunction "NC_39_39") (pintype "passive"))
    )
    (net (code "129") (name "unconnected-(U6000B-NC_80-Pad80)") (class "Default")
      (node (ref "U6000") (pin "80") (pinfunction "NC_80_80") (pintype "passive"))
    )
    (net (code "130") (name "unconnected-(U6000B-NC_81-Pad81)") (class "Default")
      (node (ref "U6000") (pin "81") (pinfunction "NC_81_81") (pintype "passive"))
    )
    (net (code "131") (name "unconnected-(U6000B-NC_107-Pad107)") (class "Default")
      (node (ref "U6000") (pin "107") (pinfunction "NC_107_107") (pintype "passive"))
    )
    (net (code "132") (name "unconnected-(U6000B-NC_113-Pad113)") (class "Default")
      (node (ref "U6000") (pin "113") (pinfunction "NC_113_113") (pintype "passive"))
    )
    (net (code "133") (name "unconnected-(U6000B-NC_117-Pad117)") (class "Default")
      (node (ref "U6000") (pin "117") (pinfunction "NC_117_117") (pintype "passive"))
    )
    (net (code "134") (name "unconnected-(U6000B-NC_119-Pad119)") (class "Default")
      (node (ref "U6000") (pin "119") (pinfunction "NC_119_119") (pintype "passive"))
    )
    (net (code "135") (name "unconnected-(U6000B-NC_122-Pad122)") (class "Default")
      (node (ref "U6000") (pin "122") (pinfunction "NC_122_122") (pintype "passive"))
    )
    (net (code "136") (name "unconnected-(U6000B-NC_124-Pad124)") (class "Default")
      (node (ref "U6000") (pin "124") (pinfunction "NC_124_124") (pintype "passive"))
    )
    (net (code "137") (name "unconnected-(U6000B-NC_131-Pad131)") (class "Default")
      (node (ref "U6000") (pin "131") (pinfunction "NC_131_131") (pintype "passive"))
    )
  )
)
